# power_supply_module.net
KiCad netlist of a schematic drawn in EAGLE
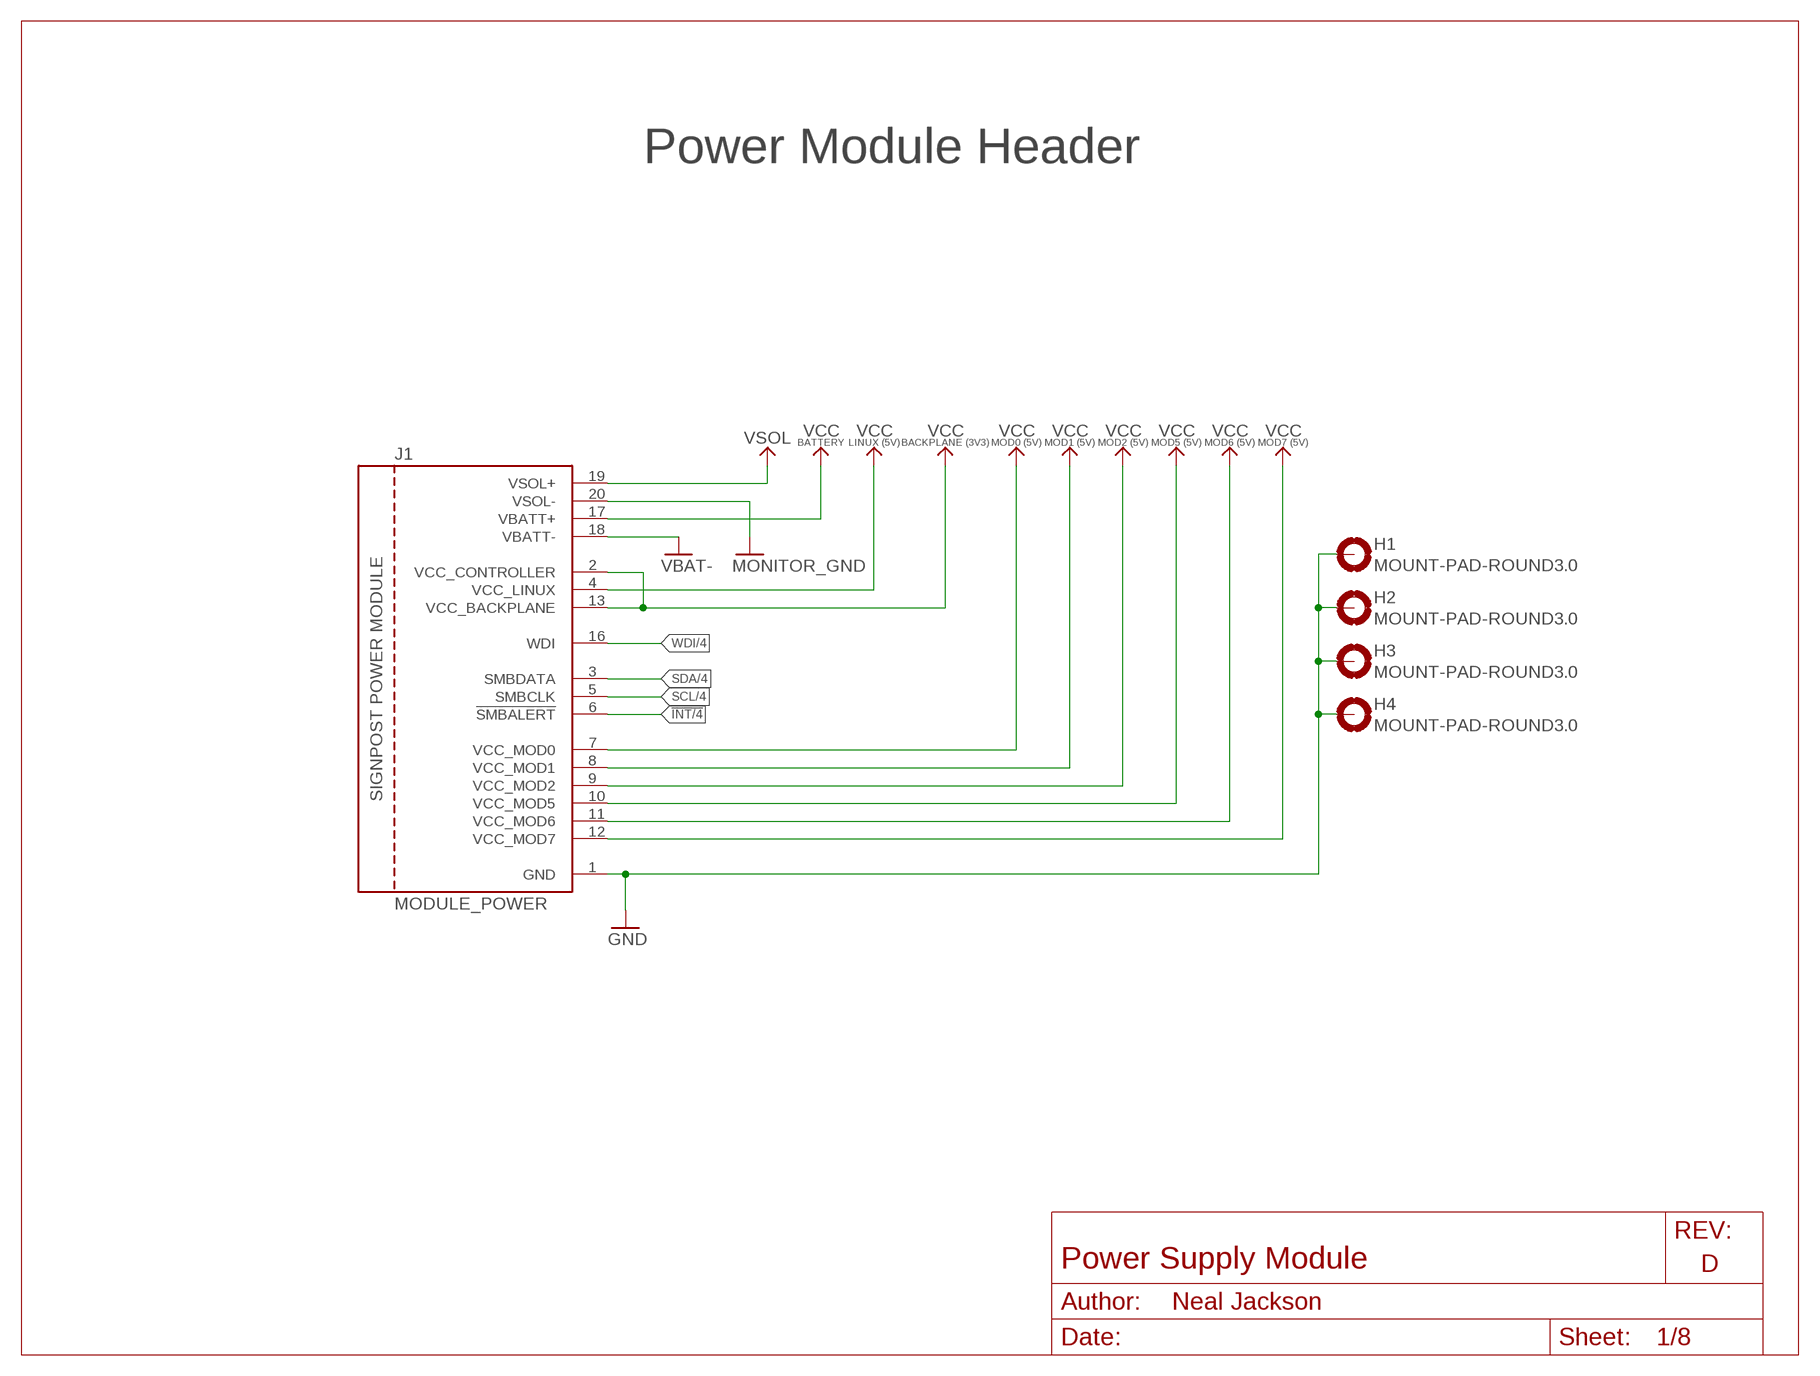
[diagram p0: schematic, sheet 1]
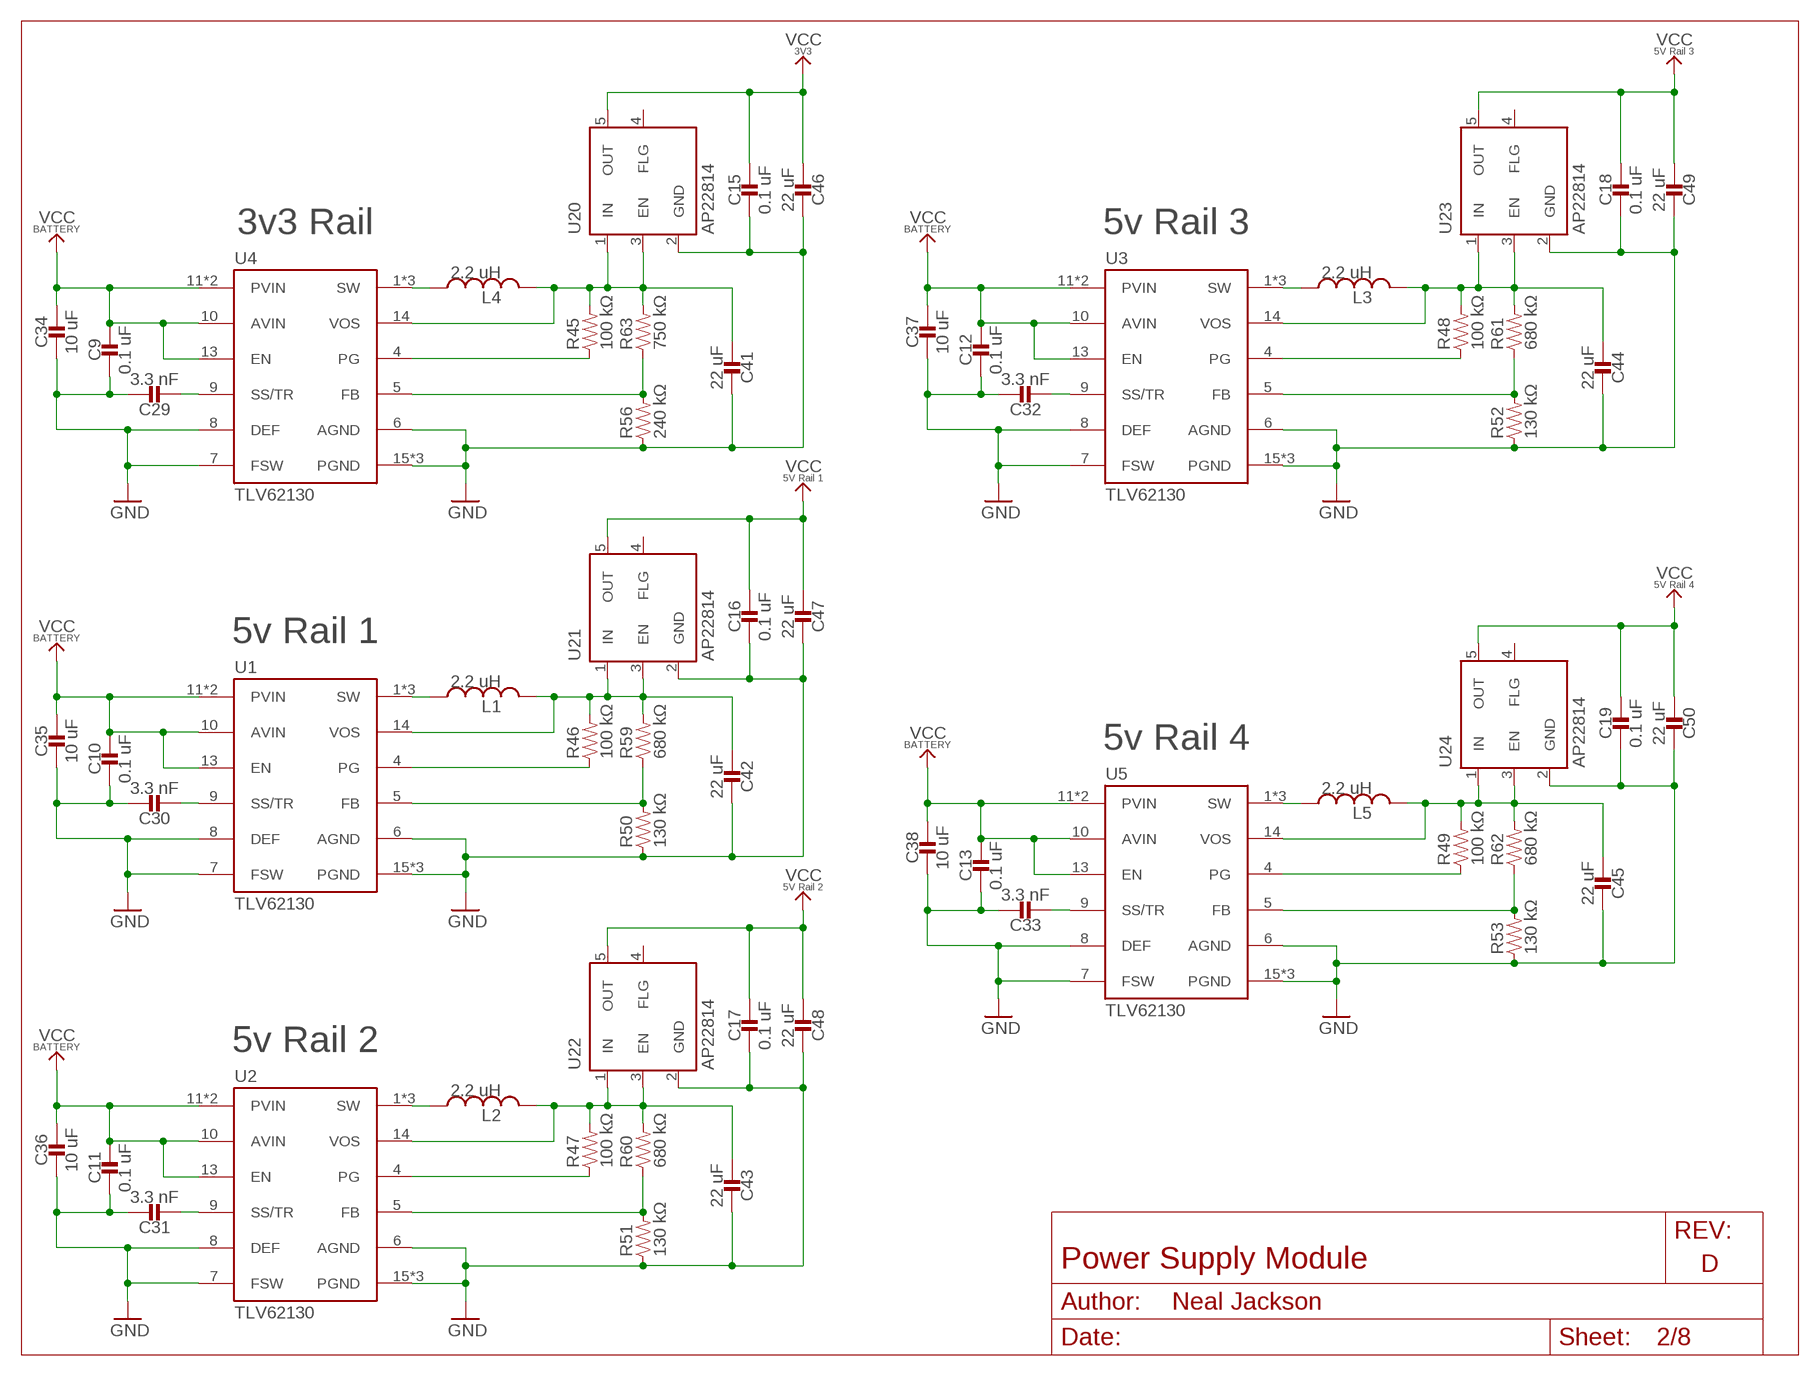
[diagram p1: schematic, sheet 2]
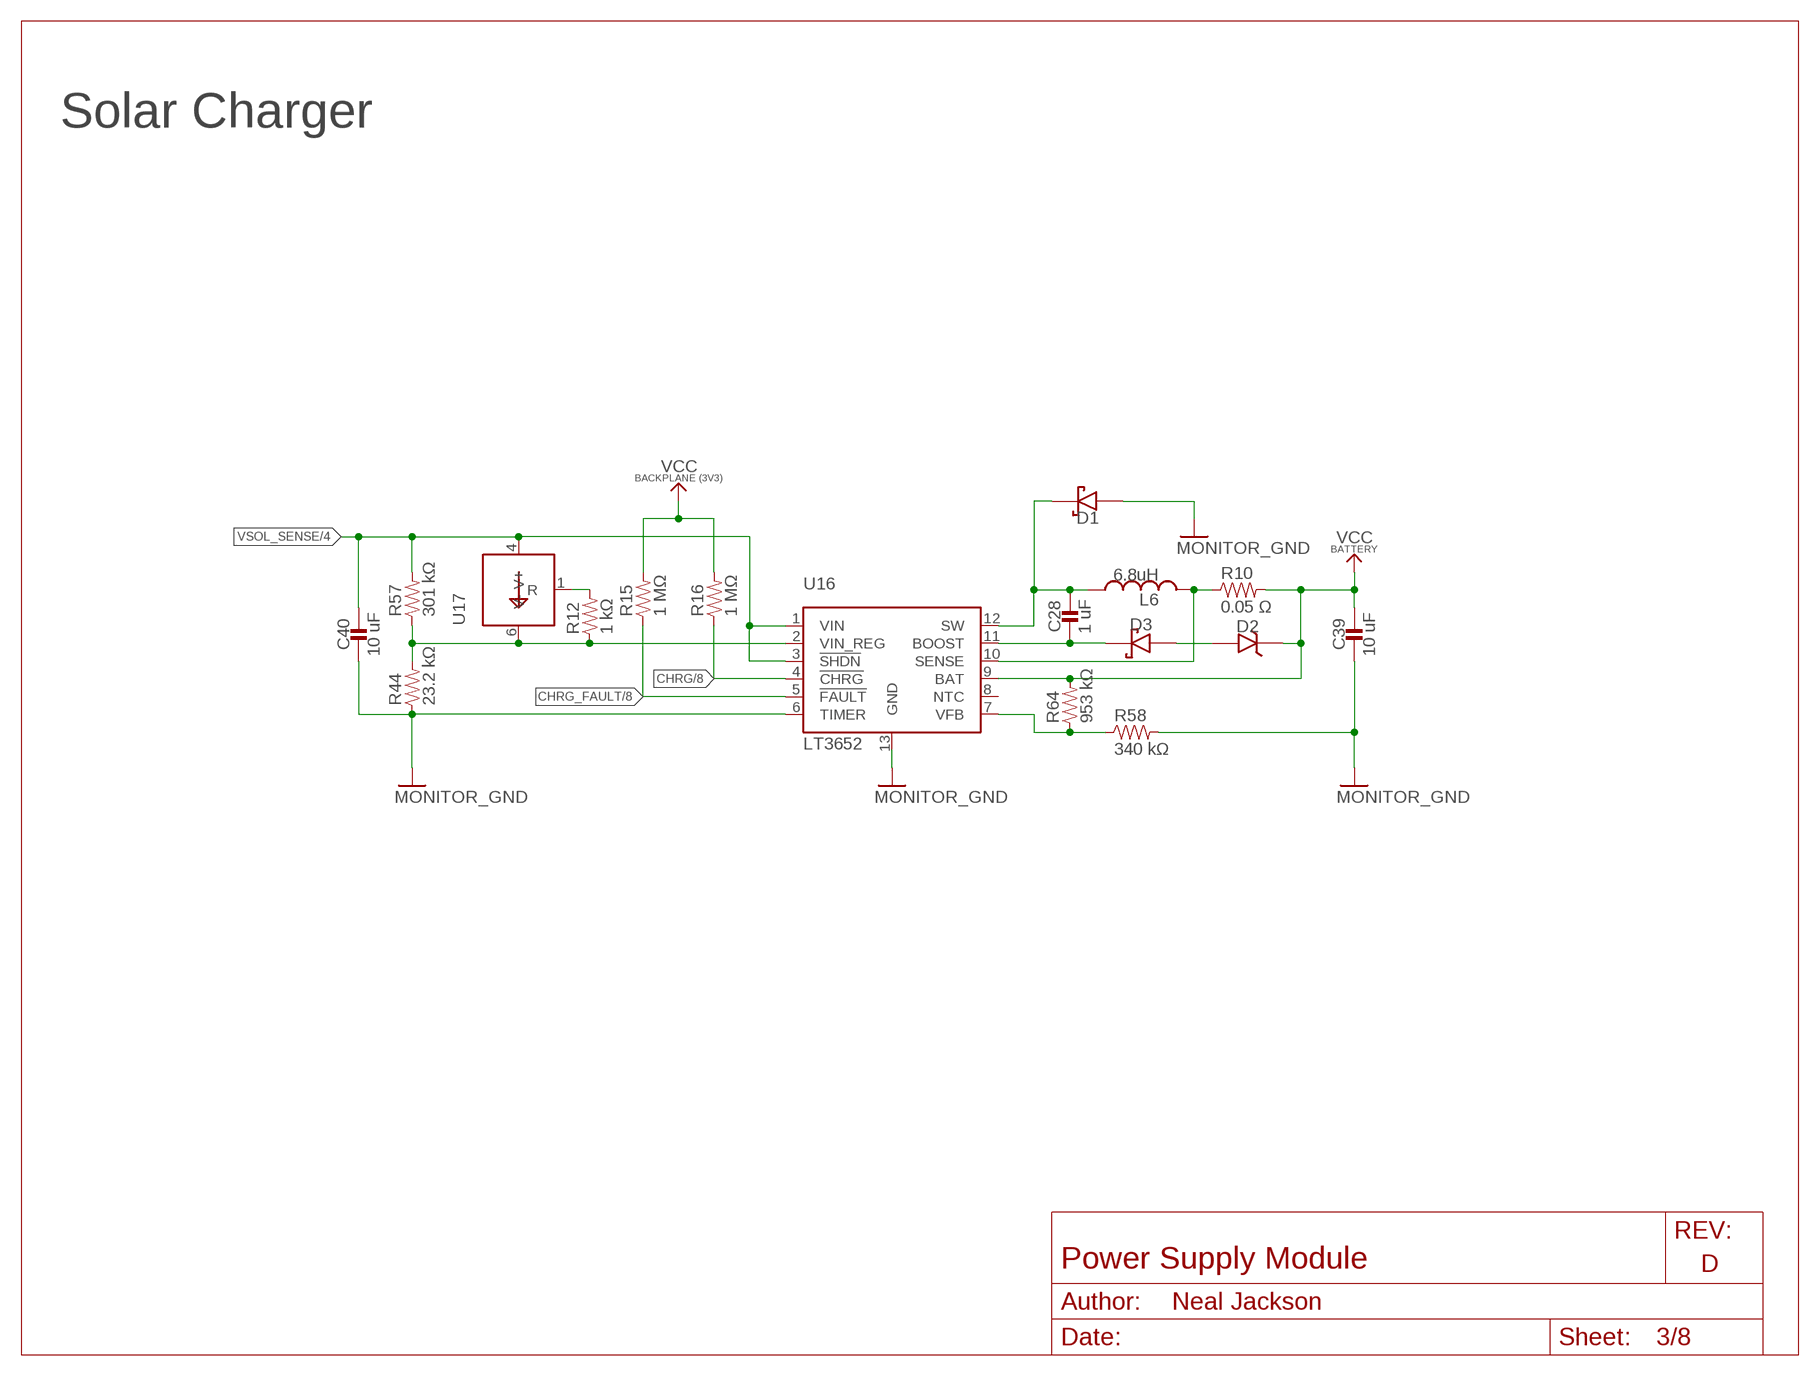
[diagram p2: schematic, sheet 3]
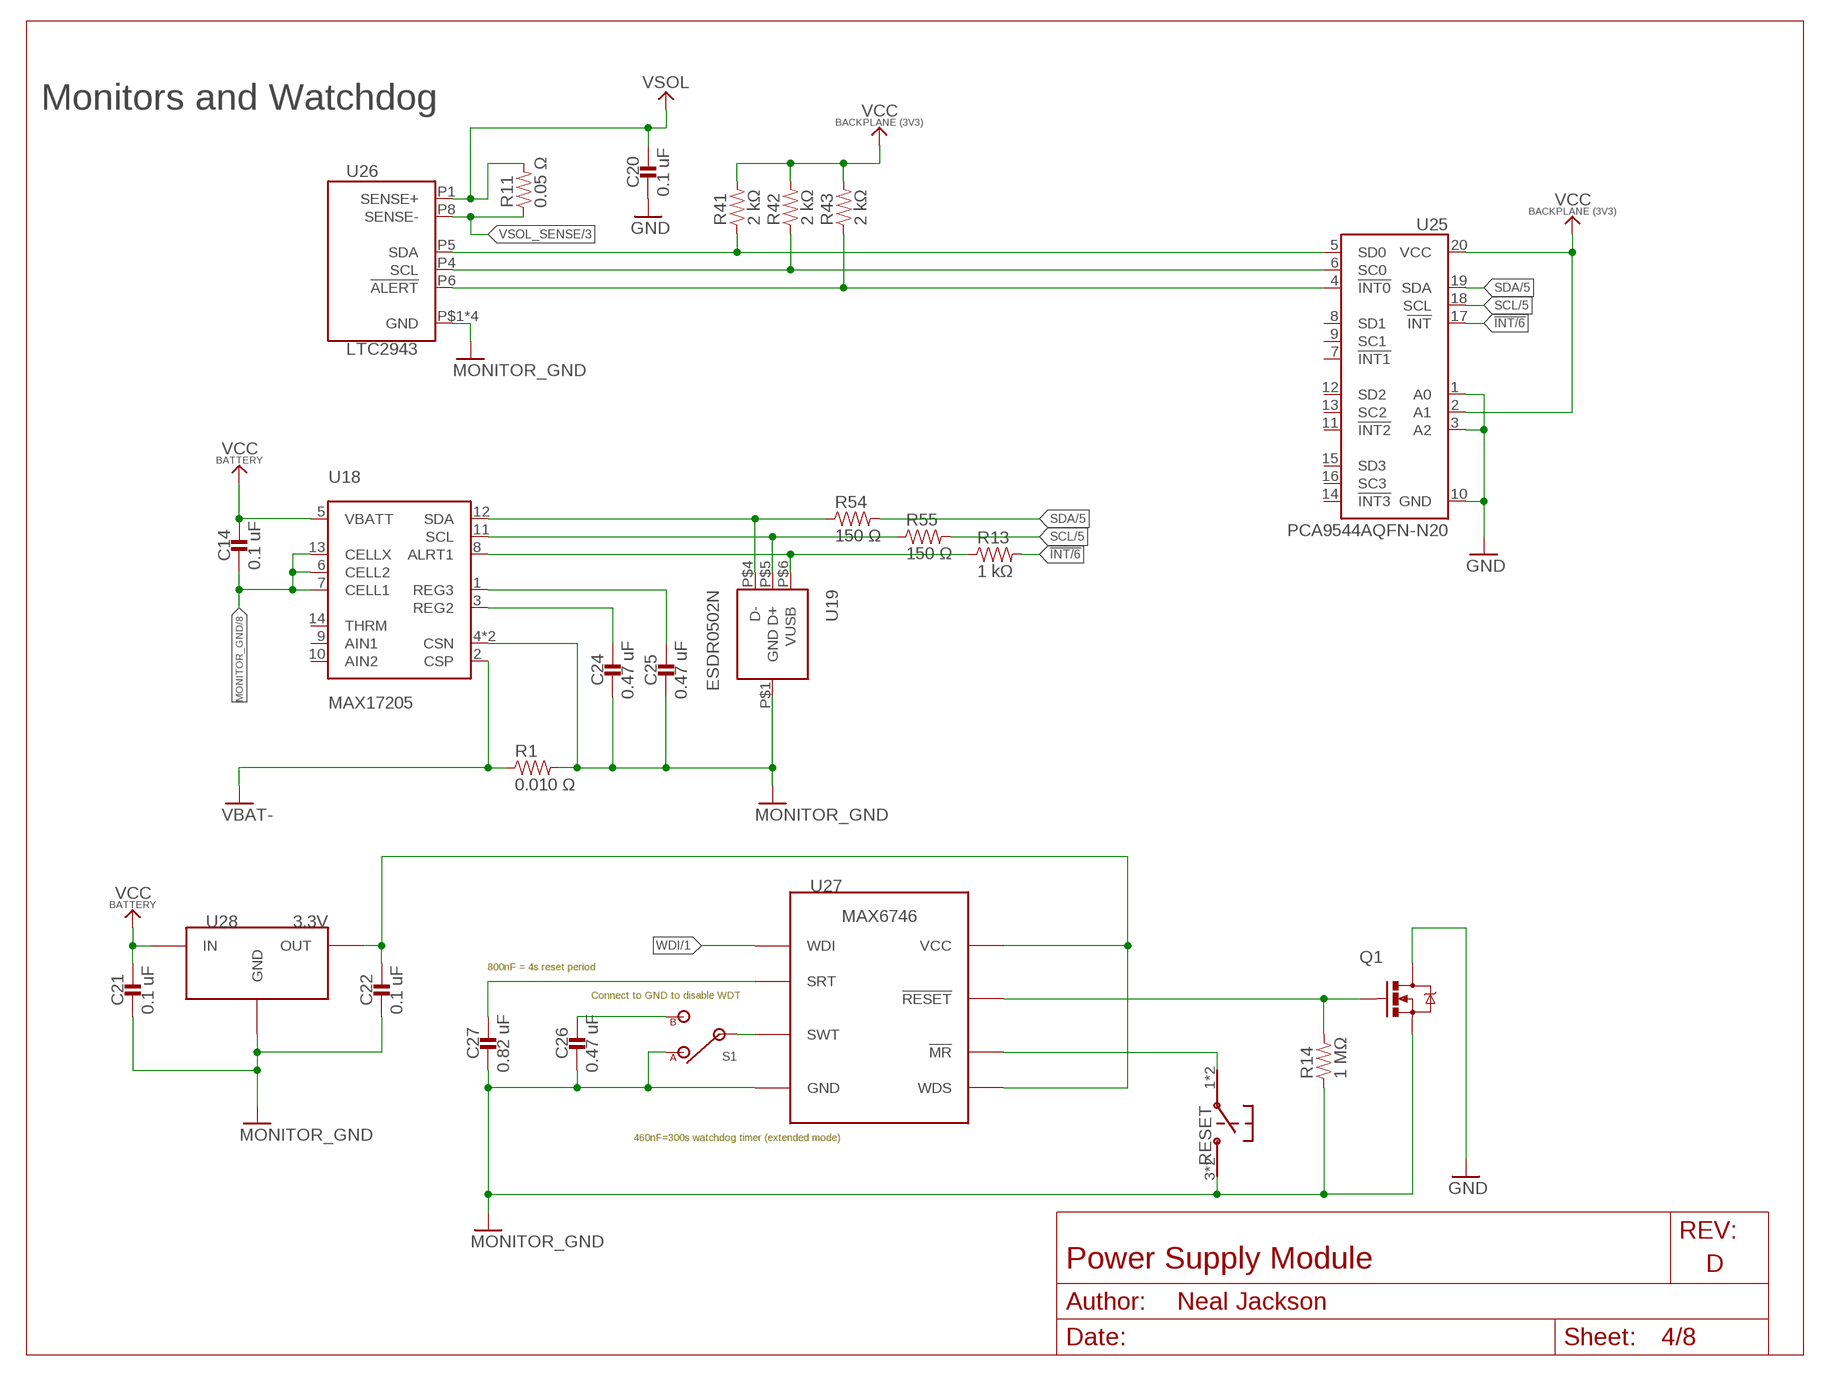
[diagram p3: schematic, sheet 4]
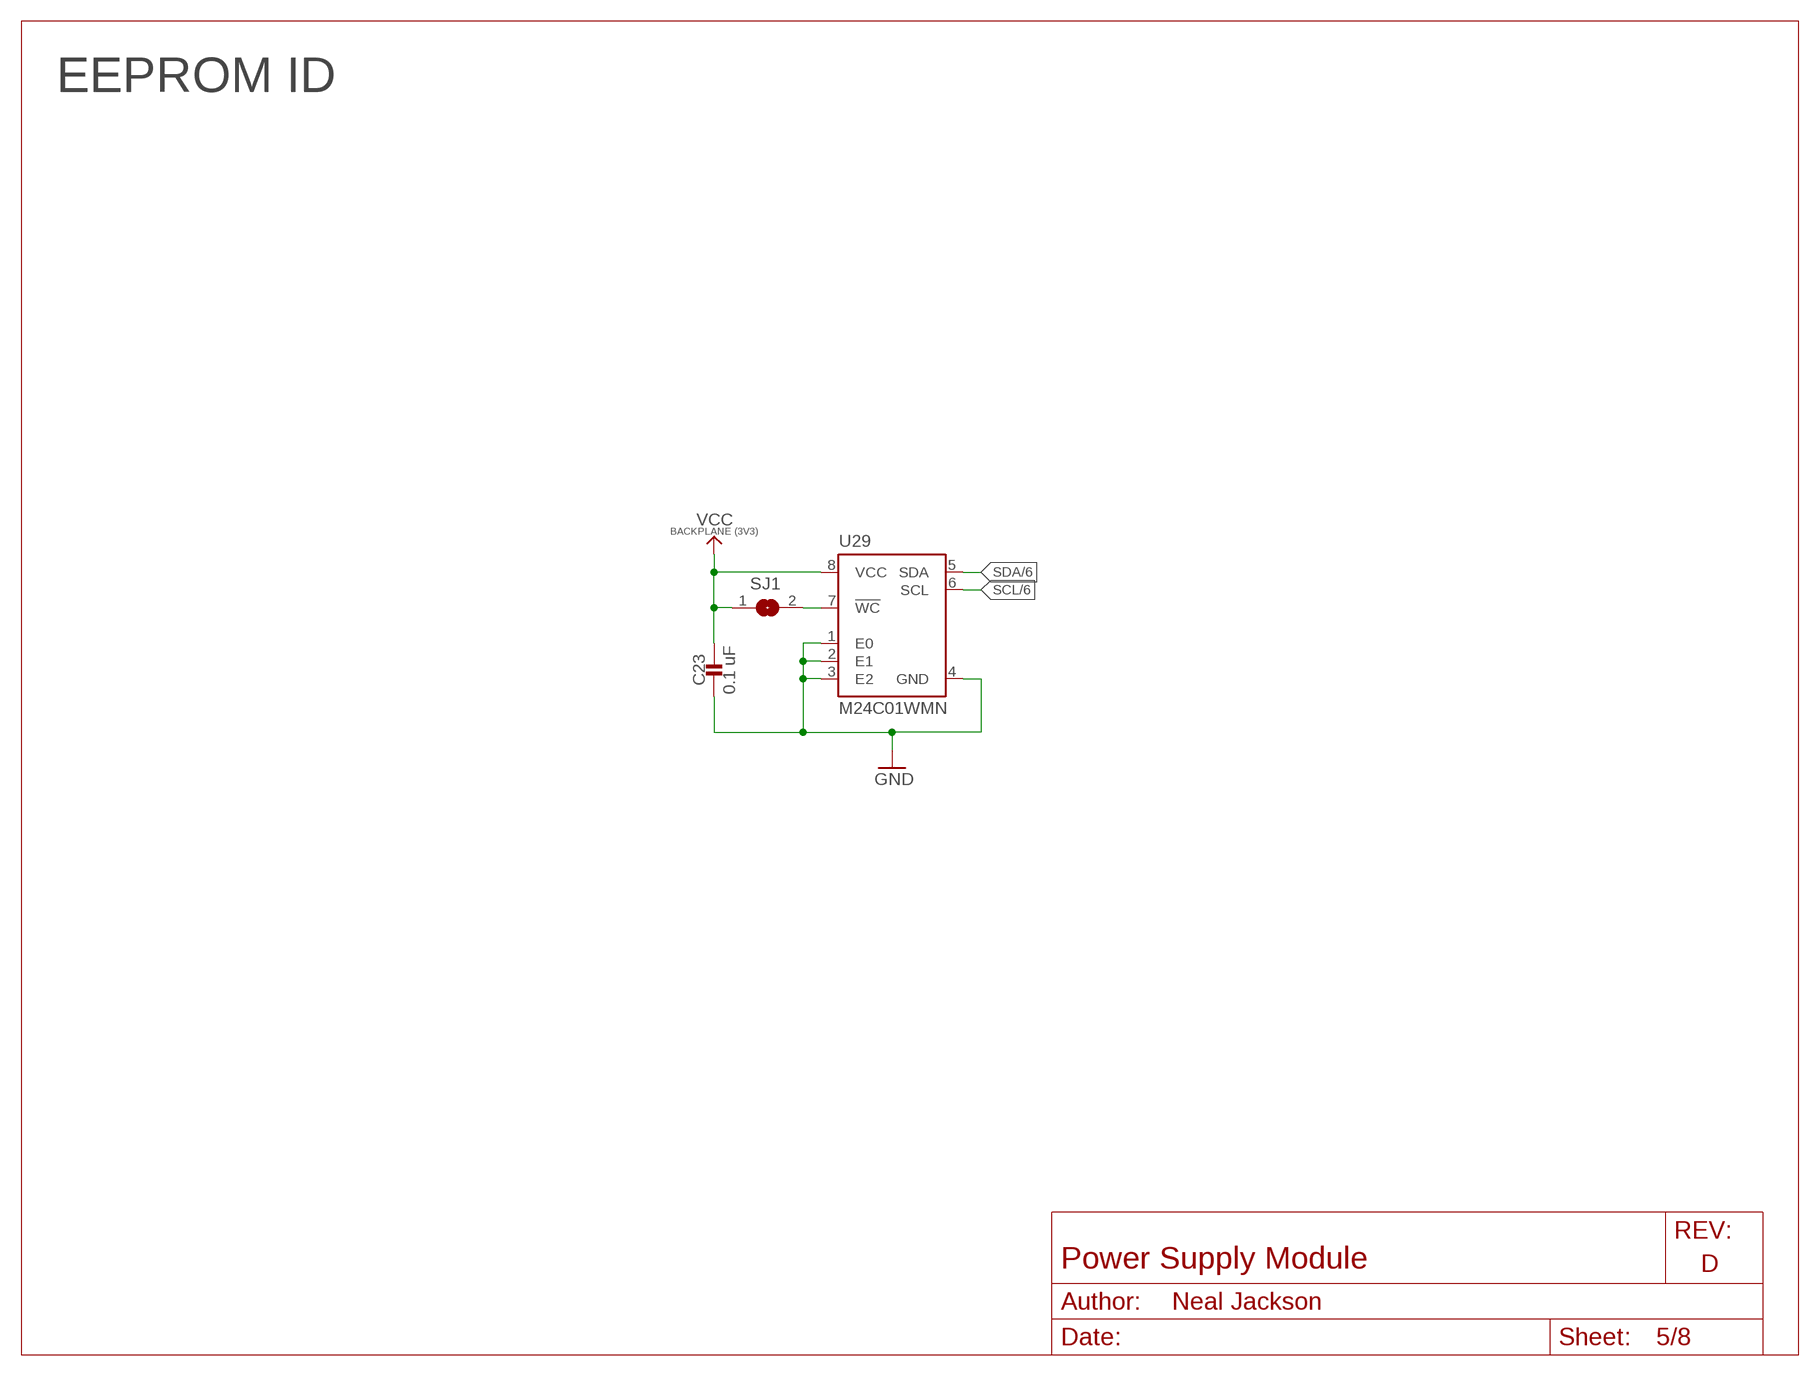
[diagram p4: schematic, sheet 5]
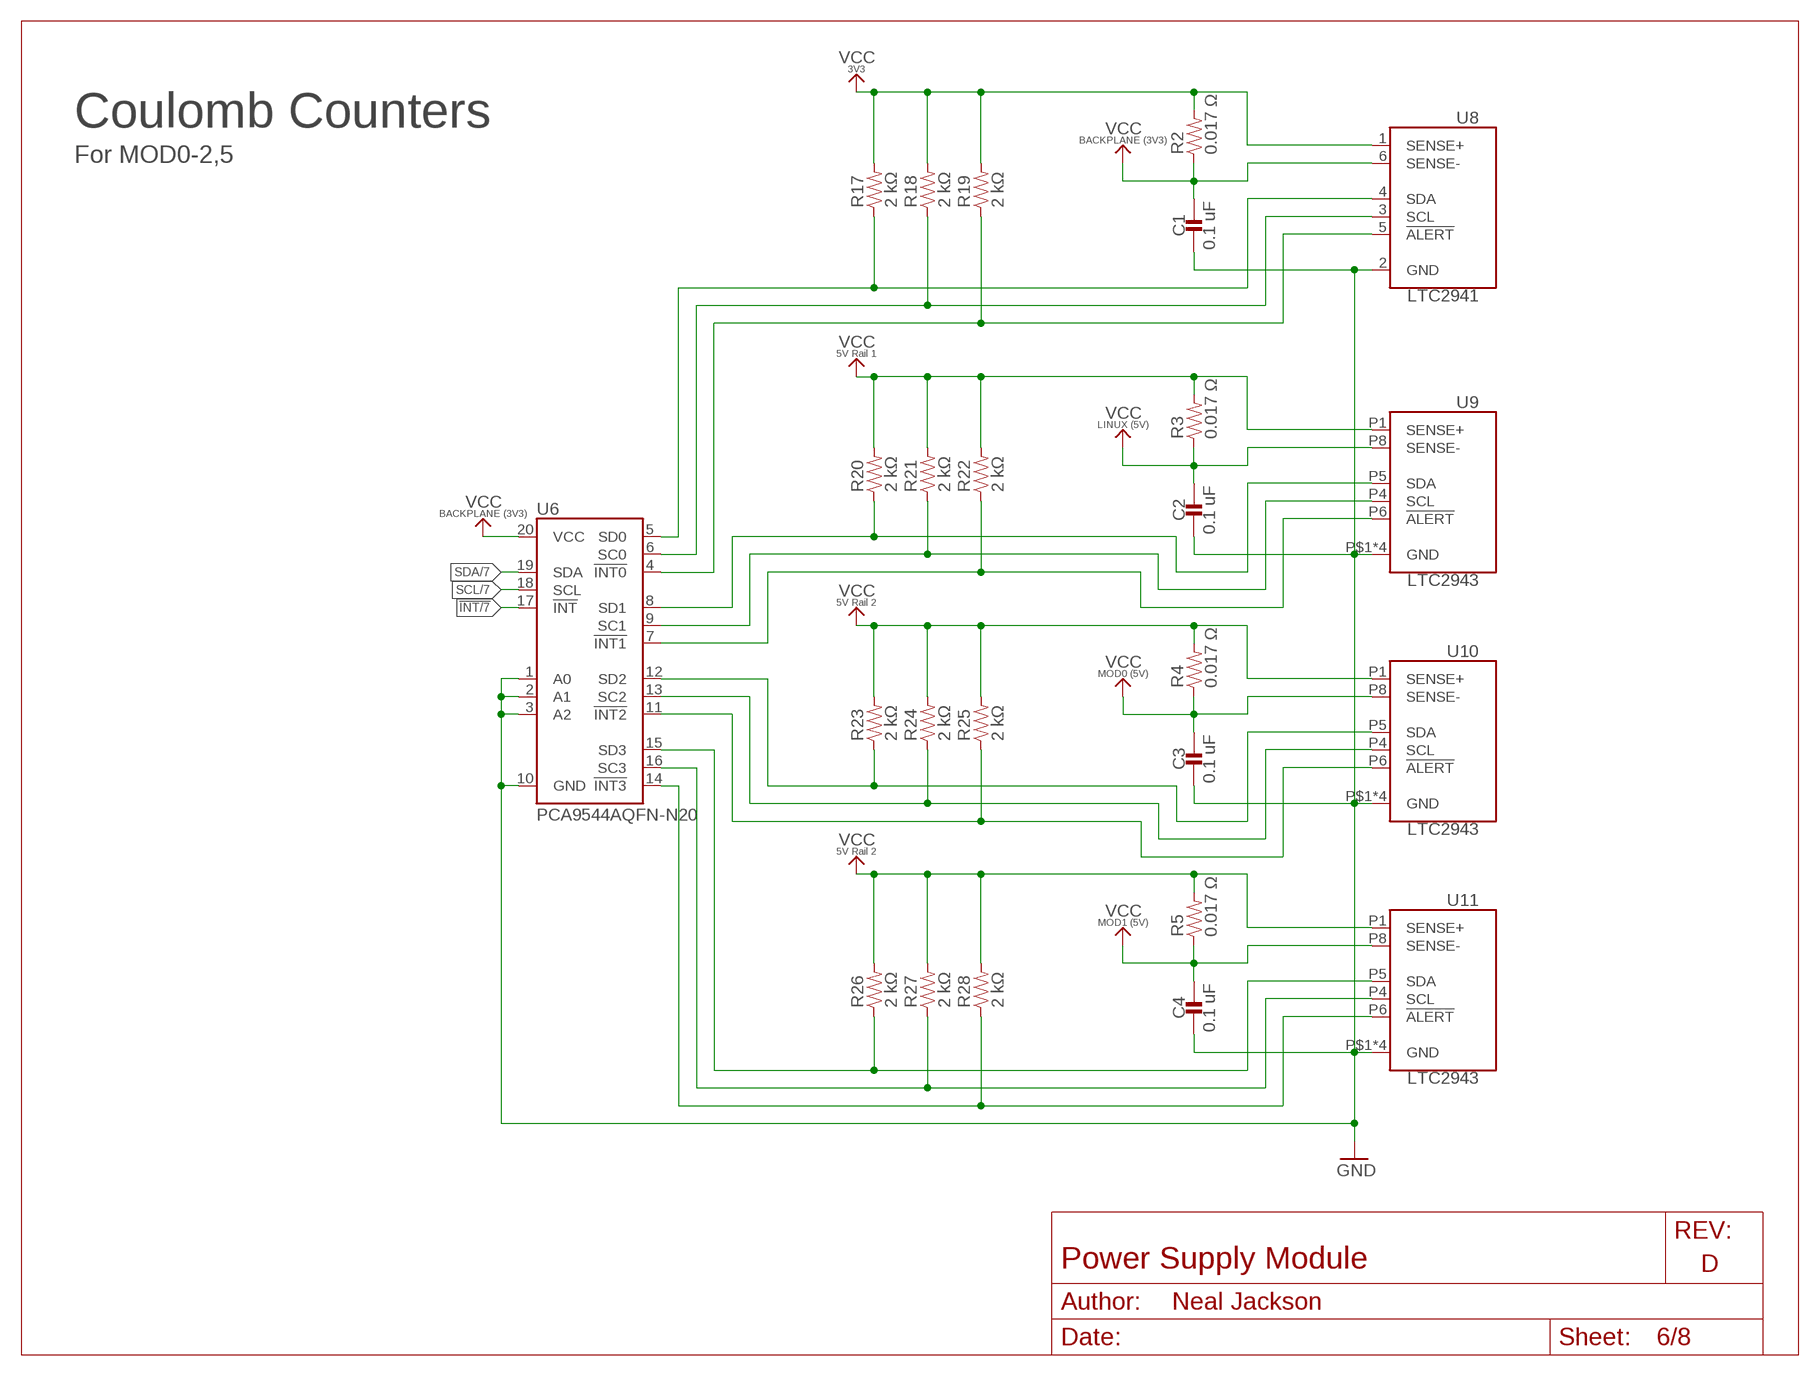
[diagram p5: schematic, sheet 6]
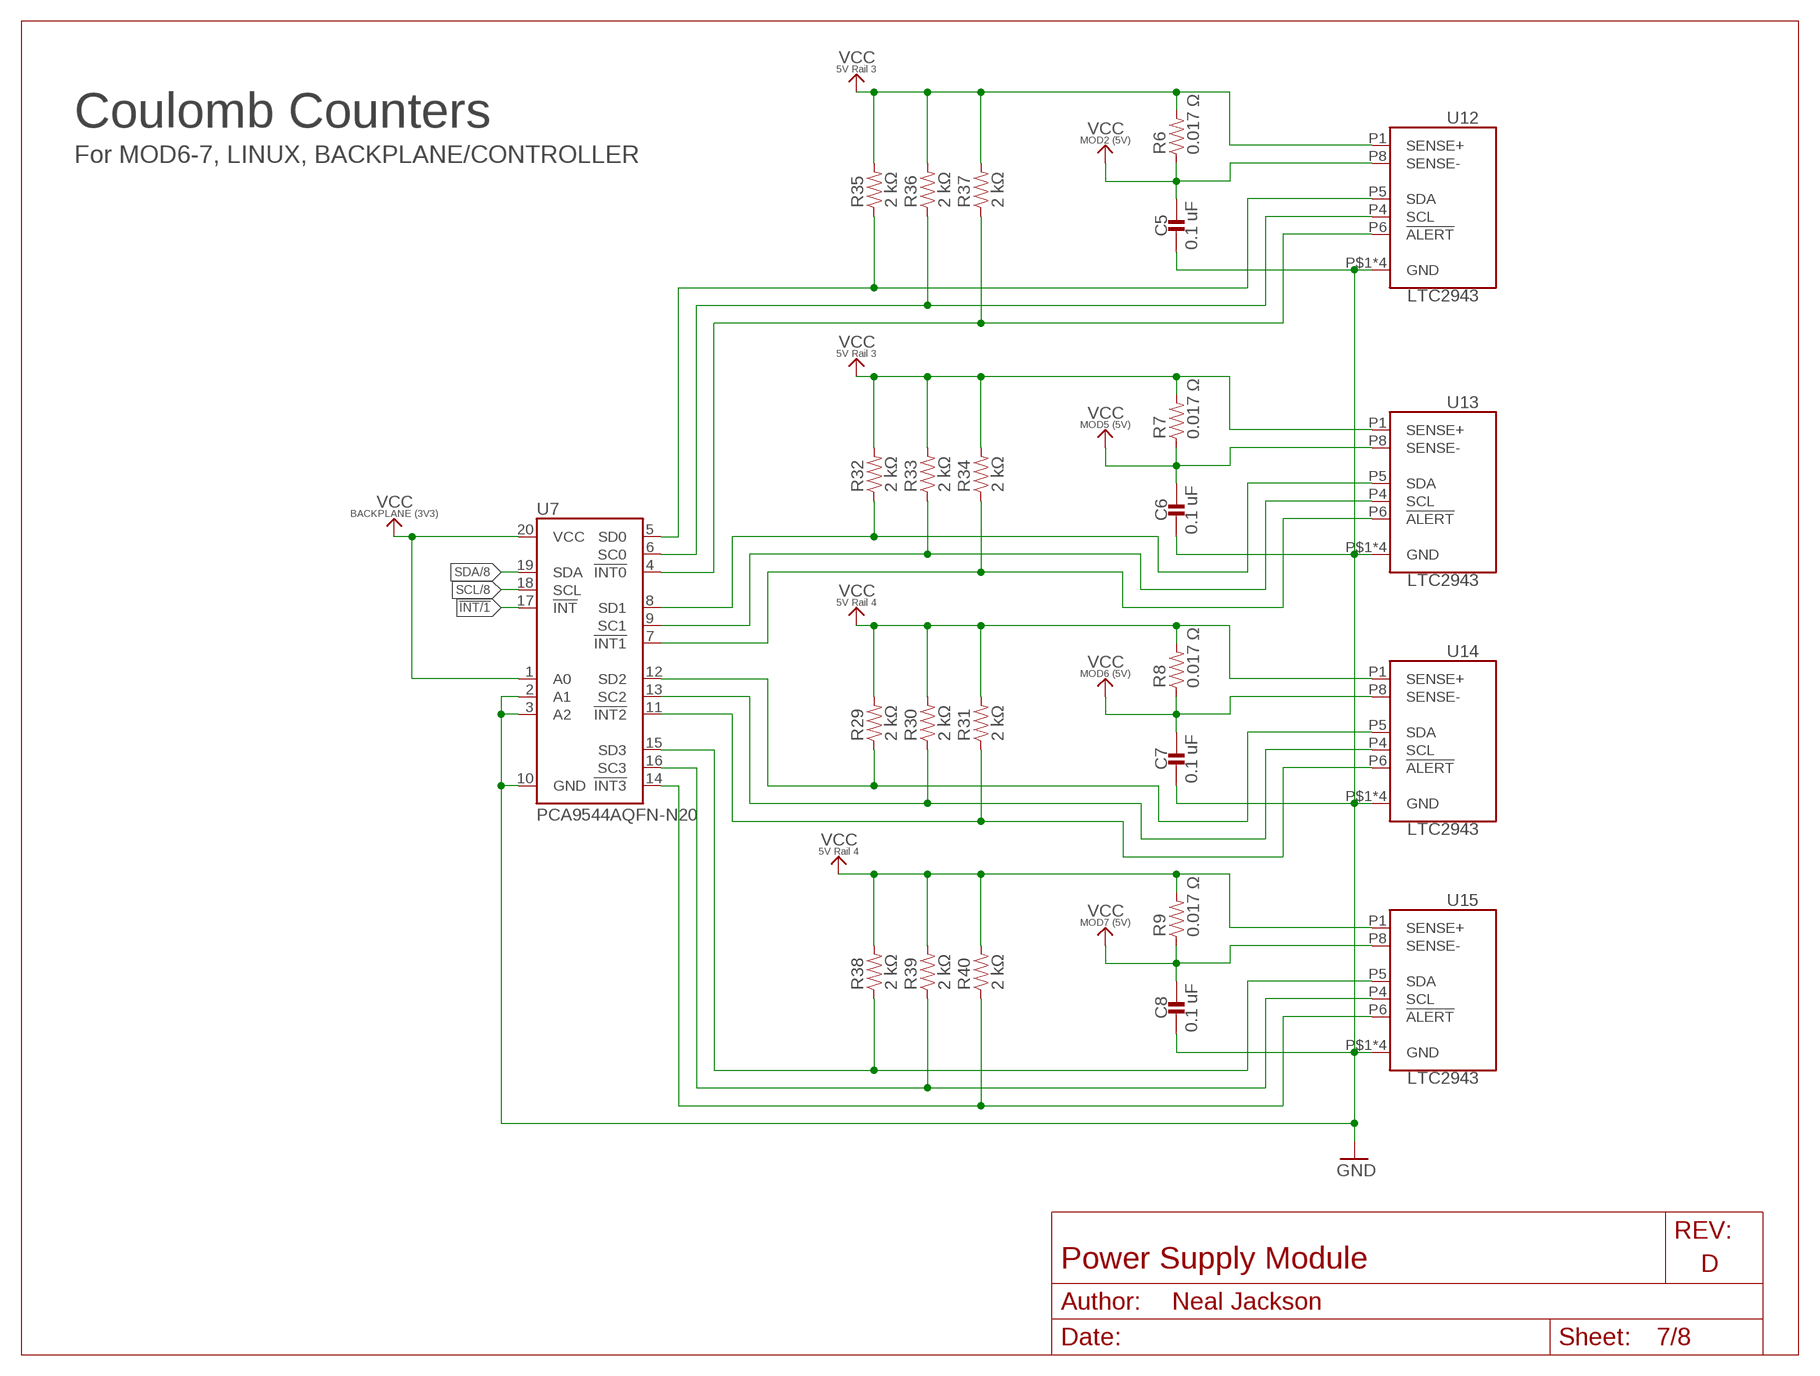
[diagram p6: schematic, sheet 7]
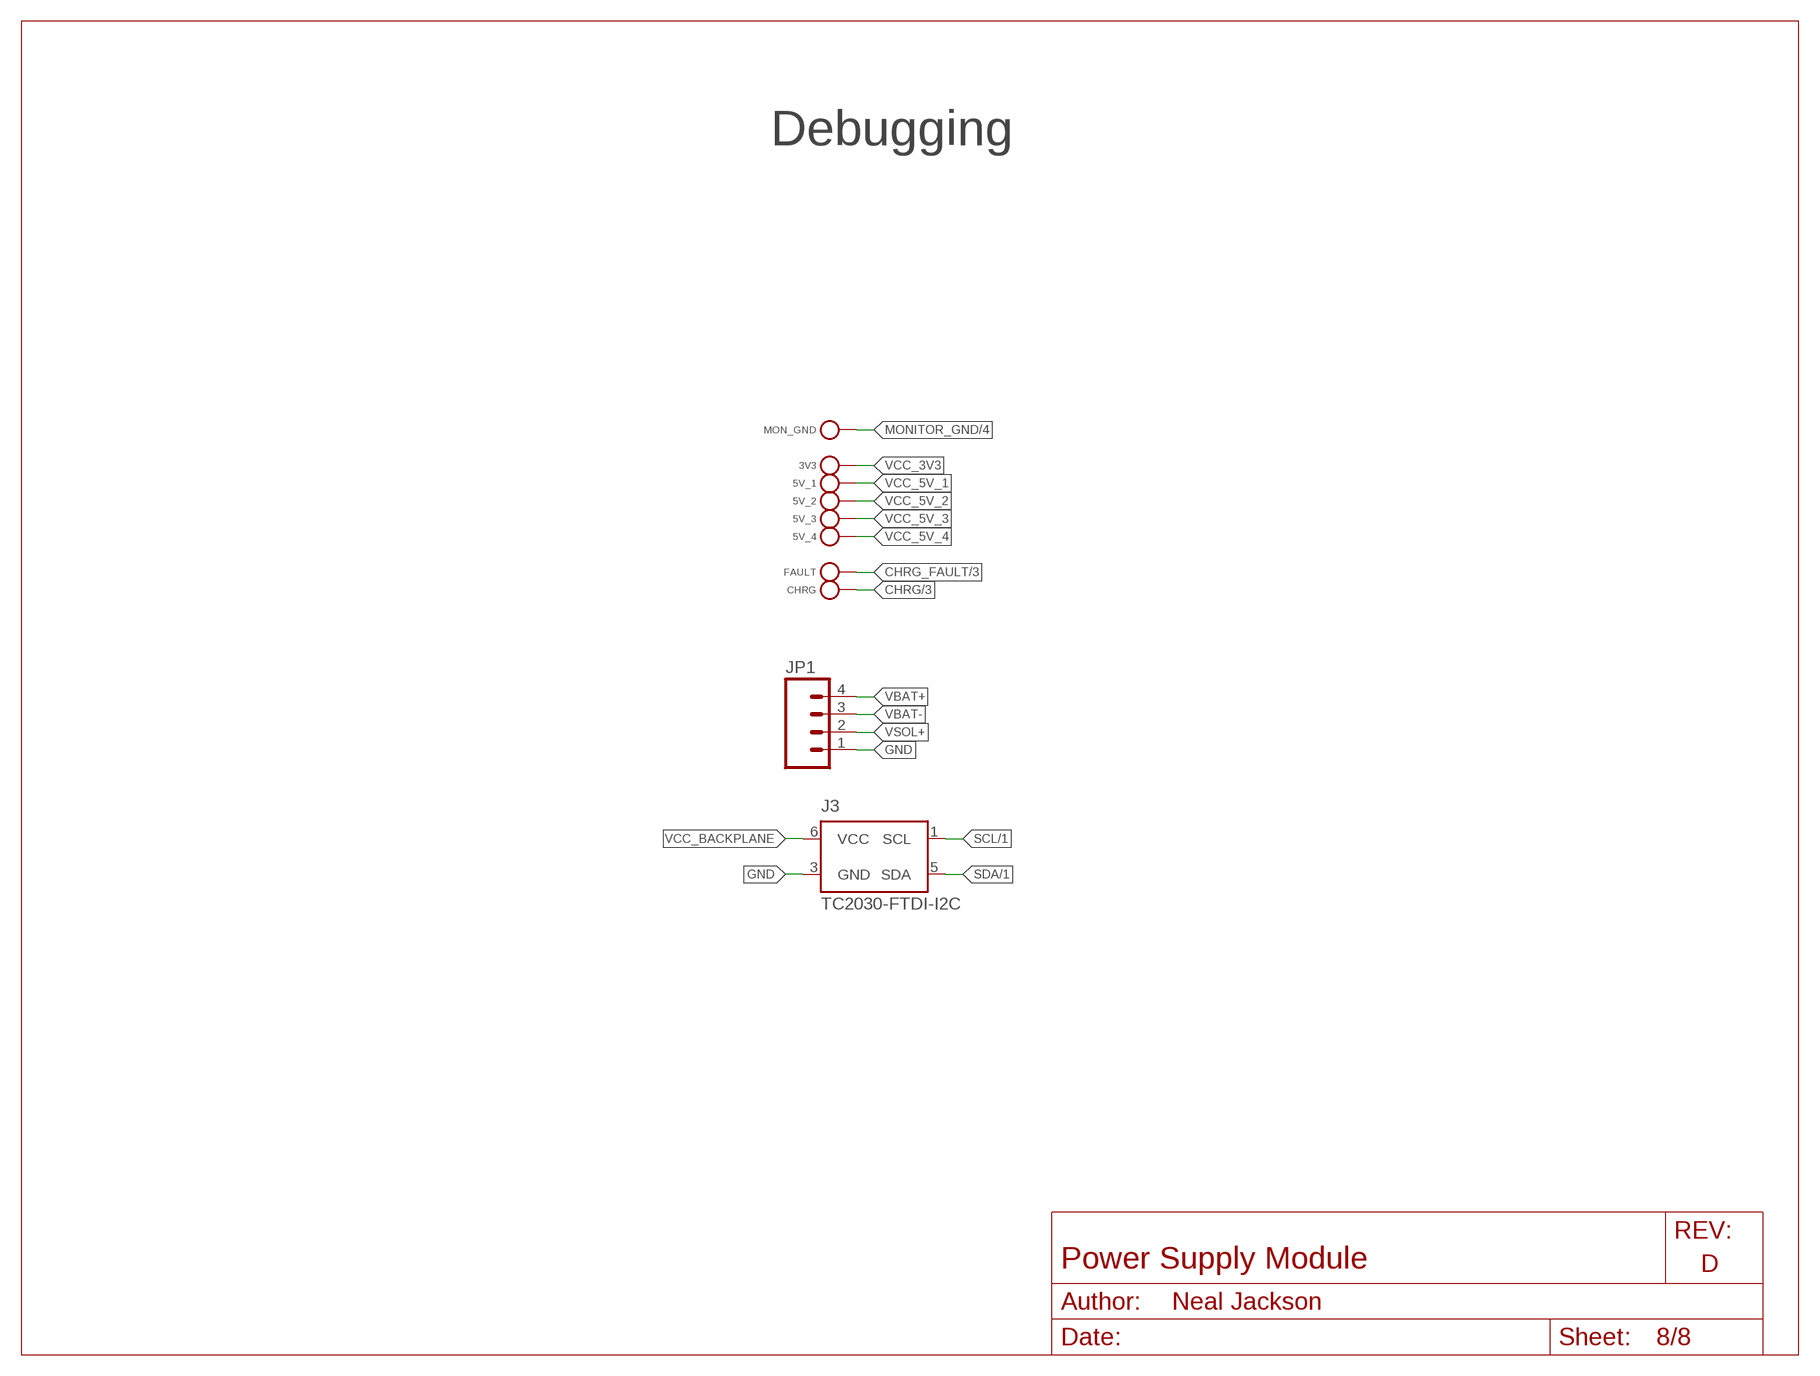
[diagram p7: schematic, sheet 8]

(export (version "E")
  (design (tool "Eeschema 10.0.6"))
  (components
    (comp (ref "3V3")
      (value "TEST_POINT_0.040IN")
      (footprint "eagle-import:TESTPOINT_0.040IN")
      (libsource (lib "eagle-import") (part "TEST_POINT_0.040IN"))
    )
    (comp (ref "5V_1")
      (value "TEST_POINT_0.040IN")
      (footprint "eagle-import:TESTPOINT_0.040IN")
      (libsource (lib "eagle-import") (part "TEST_POINT_0.040IN"))
    )
    (comp (ref "5V_2")
      (value "TEST_POINT_0.040IN")
      (footprint "eagle-import:TESTPOINT_0.040IN")
      (libsource (lib "eagle-import") (part "TEST_POINT_0.040IN"))
    )
    (comp (ref "5V_3")
      (value "TEST_POINT_0.040IN")
      (footprint "eagle-import:TESTPOINT_0.040IN")
      (libsource (lib "eagle-import") (part "TEST_POINT_0.040IN"))
    )
    (comp (ref "5V_4")
      (value "TEST_POINT_0.040IN")
      (footprint "eagle-import:TESTPOINT_0.040IN")
      (libsource (lib "eagle-import") (part "TEST_POINT_0.040IN"))
    )
    (comp (ref "CHRG")
      (value "TEST_POINT_0.040IN")
      (footprint "eagle-import:TESTPOINT_0.040IN")
      (libsource (lib "eagle-import") (part "TEST_POINT_0.040IN"))
    )
    (comp (ref "FAULT")
      (value "TEST_POINT_0.040IN")
      (footprint "eagle-import:TESTPOINT_0.040IN")
      (libsource (lib "eagle-import") (part "TEST_POINT_0.040IN"))
    )
    (comp (ref "J3")
      (value "TC2030-FTDI-I2C")
      (footprint "eagle-import:TC2030-IDC-NL")
      (libsource (lib "eagle-import") (part "TC2030-FTDI-I2C"))
    )
    (comp (ref "JP1")
      (value "M04PTH")
      (footprint "eagle-import:1X04")
      (libsource (lib "eagle-import") (part "M04PTH"))
    )
    (comp (ref "MON_GND")
      (value "TEST_POINT_0.040IN")
      (footprint "eagle-import:TESTPOINT_0.040IN")
      (libsource (lib "eagle-import") (part "TEST_POINT_0.040IN"))
    )
    (comp (ref "C14")
      (value "0.1 uF")
      (footprint "eagle-import:0402_CAP")
      (libsource (lib "eagle-import") (part "CAPACITOR0402_CAP"))
    )
    (comp (ref "C20")
      (value "0.1 uF")
      (footprint "eagle-import:0402_CAP")
      (libsource (lib "eagle-import") (part "CAPACITOR0402_CAP"))
    )
    (comp (ref "C21")
      (value "0.1 uF")
      (footprint "eagle-import:0402_CAP")
      (libsource (lib "eagle-import") (part "CAPACITOR0402_CAP"))
    )
    (comp (ref "C22")
      (value "0.1 uF")
      (footprint "eagle-import:0402_CAP")
      (libsource (lib "eagle-import") (part "CAPACITOR0402_CAP"))
    )
    (comp (ref "C24")
      (value "0.47 uF")
      (footprint "eagle-import:0402_CAP")
      (libsource (lib "eagle-import") (part "CAPACITOR0402_CAP"))
    )
    (comp (ref "C25")
      (value "0.47 uF")
      (footprint "eagle-import:0402_CAP")
      (libsource (lib "eagle-import") (part "CAPACITOR0402_CAP"))
    )
    (comp (ref "C26")
      (value "0.47 uF")
      (footprint "eagle-import:0402_CAP")
      (libsource (lib "eagle-import") (part "CAPACITOR0402_CAP"))
    )
    (comp (ref "C27")
      (value "0.82 uF")
      (footprint "eagle-import:0402_CAP")
      (libsource (lib "eagle-import") (part "CAPACITOR0402_CAP"))
    )
    (comp (ref "Q1")
      (value "MOSFET-NCHANNELFDD8580")
      (footprint "eagle-import:DPAK")
      (libsource (lib "eagle-import") (part "MOSFET-NCHANNELFDD8580"))
    )
    (comp (ref "R1")
      (value "0.010 Ω")
      (footprint "eagle-import:0805_RES")
      (libsource (lib "eagle-import") (part "RESISTOR0805_RES"))
    )
    (comp (ref "R11")
      (value "0.05 Ω")
      (footprint "eagle-import:0805_RES")
      (libsource (lib "eagle-import") (part "RESISTOR0805_RES"))
    )
    (comp (ref "R13")
      (value "1 kΩ")
      (footprint "eagle-import:0402_RES")
      (libsource (lib "eagle-import") (part "RESISTOR0402_RES"))
    )
    (comp (ref "R14")
      (value "1 MΩ")
      (footprint "eagle-import:0402_RES")
      (libsource (lib "eagle-import") (part "RESISTOR0402_RES"))
    )
    (comp (ref "R41")
      (value "2 kΩ")
      (footprint "eagle-import:0402_RES")
      (libsource (lib "eagle-import") (part "RESISTOR0402_RES"))
    )
    (comp (ref "R42")
      (value "2 kΩ")
      (footprint "eagle-import:0402_RES")
      (libsource (lib "eagle-import") (part "RESISTOR0402_RES"))
    )
    (comp (ref "R43")
      (value "2 kΩ")
      (footprint "eagle-import:0402_RES")
      (libsource (lib "eagle-import") (part "RESISTOR0402_RES"))
    )
    (comp (ref "R54")
      (value "150 Ω")
      (footprint "eagle-import:0402_RES")
      (libsource (lib "eagle-import") (part "RESISTOR0402_RES"))
    )
    (comp (ref "R55")
      (value "150 Ω")
      (footprint "eagle-import:0402_RES")
      (libsource (lib "eagle-import") (part "RESISTOR0402_RES"))
    )
    (comp (ref "RESET")
      (value "PTS810SJ")
      (footprint "eagle-import:PTS810SJ")
      (libsource (lib "eagle-import") (part "PTS810SJ"))
    )
    (comp (ref "S1")
      (value "TE_SSA12/SPDT")
      (footprint "eagle-import:TE_SSA12_SPDT")
      (libsource (lib "eagle-import") (part "TE_SSA12/SPDT"))
    )
    (comp (ref "U18")
      (value "MAX17205")
      (footprint "eagle-import:14-TDFN")
      (libsource (lib "eagle-import") (part "MAX17205"))
    )
    (comp (ref "U19")
      (value "ESDR0502N")
      (footprint "eagle-import:UDFN-6")
      (libsource (lib "eagle-import") (part "ESDR0502N"))
    )
    (comp (ref "U25")
      (value "PCA9544AQFN-N20")
      (footprint "eagle-import:QFN-N20")
      (libsource (lib "eagle-import") (part "PCA9544AQFN-N20"))
    )
    (comp (ref "U26")
      (value "LTC2943")
      (footprint "eagle-import:DFN-8")
      (libsource (lib "eagle-import") (part "LTC2943"))
    )
    (comp (ref "U27")
      (value "MAX6746")
      (footprint "eagle-import:SOT-23-8")
      (libsource (lib "eagle-import") (part "MAX6746"))
    )
    (comp (ref "U28")
      (value "3.3V")
      (footprint "eagle-import:SOT-23")
      (fields (field (name "DIGIKEY") "ZMR330FCT-ND"))
      (libsource (lib "eagle-import") (part "TILM34803.3V"))
    )
    (comp (ref "H1")
      (value "MOUNT-PAD-ROUND3.0")
      (footprint "eagle-import:3,0-PAD")
      (libsource (lib "eagle-import") (part "MOUNT-PAD-ROUND3.0"))
    )
    (comp (ref "H2")
      (value "MOUNT-PAD-ROUND3.0")
      (footprint "eagle-import:3,0-PAD")
      (libsource (lib "eagle-import") (part "MOUNT-PAD-ROUND3.0"))
    )
    (comp (ref "H3")
      (value "MOUNT-PAD-ROUND3.0")
      (footprint "eagle-import:3,0-PAD")
      (libsource (lib "eagle-import") (part "MOUNT-PAD-ROUND3.0"))
    )
    (comp (ref "H4")
      (value "MOUNT-PAD-ROUND3.0")
      (footprint "eagle-import:3,0-PAD")
      (libsource (lib "eagle-import") (part "MOUNT-PAD-ROUND3.0"))
    )
    (comp (ref "J1")
      (value "MODULE_POWER")
      (footprint "eagle-import:MODULE_POWER")
      (libsource (lib "eagle-import") (part "MODULE_POWER"))
    )
    (comp (ref "C9")
      (value "0.1 uF")
      (footprint "eagle-import:0402_CAP")
      (libsource (lib "eagle-import") (part "CAPACITOR0402_CAP"))
    )
    (comp (ref "C10")
      (value "0.1 uF")
      (footprint "eagle-import:0402_CAP")
      (libsource (lib "eagle-import") (part "CAPACITOR0402_CAP"))
    )
    (comp (ref "C11")
      (value "0.1 uF")
      (footprint "eagle-import:0402_CAP")
      (libsource (lib "eagle-import") (part "CAPACITOR0402_CAP"))
    )
    (comp (ref "C12")
      (value "0.1 uF")
      (footprint "eagle-import:0402_CAP")
      (libsource (lib "eagle-import") (part "CAPACITOR0402_CAP"))
    )
    (comp (ref "C13")
      (value "0.1 uF")
      (footprint "eagle-import:0402_CAP")
      (libsource (lib "eagle-import") (part "CAPACITOR0402_CAP"))
    )
    (comp (ref "C15")
      (value "0.1 uF")
      (footprint "eagle-import:0402_CAP")
      (libsource (lib "eagle-import") (part "CAPACITOR0402_CAP"))
    )
    (comp (ref "C16")
      (value "0.1 uF")
      (footprint "eagle-import:0402_CAP")
      (libsource (lib "eagle-import") (part "CAPACITOR0402_CAP"))
    )
    (comp (ref "C17")
      (value "0.1 uF")
      (footprint "eagle-import:0402_CAP")
      (libsource (lib "eagle-import") (part "CAPACITOR0402_CAP"))
    )
    (comp (ref "C18")
      (value "0.1 uF")
      (footprint "eagle-import:0402_CAP")
      (libsource (lib "eagle-import") (part "CAPACITOR0402_CAP"))
    )
    (comp (ref "C19")
      (value "0.1 uF")
      (footprint "eagle-import:0402_CAP")
      (libsource (lib "eagle-import") (part "CAPACITOR0402_CAP"))
    )
    (comp (ref "C29")
      (value "3.3 nF")
      (footprint "eagle-import:0402_CAP")
      (libsource (lib "eagle-import") (part "CAPACITOR0402_CAP"))
    )
    (comp (ref "C30")
      (value "3.3 nF")
      (footprint "eagle-import:0402_CAP")
      (libsource (lib "eagle-import") (part "CAPACITOR0402_CAP"))
    )
    (comp (ref "C31")
      (value "3.3 nF")
      (footprint "eagle-import:0402_CAP")
      (libsource (lib "eagle-import") (part "CAPACITOR0402_CAP"))
    )
    (comp (ref "C32")
      (value "3.3 nF")
      (footprint "eagle-import:0402_CAP")
      (libsource (lib "eagle-import") (part "CAPACITOR0402_CAP"))
    )
    (comp (ref "C33")
      (value "3.3 nF")
      (footprint "eagle-import:0402_CAP")
      (libsource (lib "eagle-import") (part "CAPACITOR0402_CAP"))
    )
    (comp (ref "C34")
      (value "10 uF")
      (footprint "eagle-import:0805_CAP")
      (libsource (lib "eagle-import") (part "CAPACITOR0805_CAP"))
    )
    (comp (ref "C35")
      (value "10 uF")
      (footprint "eagle-import:0805_CAP")
      (libsource (lib "eagle-import") (part "CAPACITOR0805_CAP"))
    )
    (comp (ref "C36")
      (value "10 uF")
      (footprint "eagle-import:0805_CAP")
      (libsource (lib "eagle-import") (part "CAPACITOR0805_CAP"))
    )
    (comp (ref "C37")
      (value "10 uF")
      (footprint "eagle-import:0805_CAP")
      (libsource (lib "eagle-import") (part "CAPACITOR0805_CAP"))
    )
    (comp (ref "C38")
      (value "10 uF")
      (footprint "eagle-import:0805_CAP")
      (libsource (lib "eagle-import") (part "CAPACITOR0805_CAP"))
    )
    (comp (ref "C41")
      (value "22 uF")
      (footprint "eagle-import:0603_CAP")
      (libsource (lib "eagle-import") (part "CAPACITOR0603_CAP"))
    )
    (comp (ref "C42")
      (value "22 uF")
      (footprint "eagle-import:0603_CAP")
      (libsource (lib "eagle-import") (part "CAPACITOR0603_CAP"))
    )
    (comp (ref "C43")
      (value "22 uF")
      (footprint "eagle-import:0603_CAP")
      (libsource (lib "eagle-import") (part "CAPACITOR0603_CAP"))
    )
    (comp (ref "C44")
      (value "22 uF")
      (footprint "eagle-import:0603_CAP")
      (libsource (lib "eagle-import") (part "CAPACITOR0603_CAP"))
    )
    (comp (ref "C45")
      (value "22 uF")
      (footprint "eagle-import:0603_CAP")
      (libsource (lib "eagle-import") (part "CAPACITOR0603_CAP"))
    )
    (comp (ref "C46")
      (value "22 uF")
      (footprint "eagle-import:0603_CAP")
      (libsource (lib "eagle-import") (part "CAPACITOR0603_CAP"))
    )
    (comp (ref "C47")
      (value "22 uF")
      (footprint "eagle-import:0603_CAP")
      (libsource (lib "eagle-import") (part "CAPACITOR0603_CAP"))
    )
    (comp (ref "C48")
      (value "22 uF")
      (footprint "eagle-import:0603_CAP")
      (libsource (lib "eagle-import") (part "CAPACITOR0603_CAP"))
    )
    (comp (ref "C49")
      (value "22 uF")
      (footprint "eagle-import:0603_CAP")
      (libsource (lib "eagle-import") (part "CAPACITOR0603_CAP"))
    )
    (comp (ref "C50")
      (value "22 uF")
      (footprint "eagle-import:0603_CAP")
      (libsource (lib "eagle-import") (part "CAPACITOR0603_CAP"))
    )
    (comp (ref "L1")
      (value "2.2 uH")
      (footprint "eagle-import:IHL-1212BZ-11")
      (libsource (lib "eagle-import") (part "INDUCTORIHL"))
    )
    (comp (ref "L2")
      (value "2.2 uH")
      (footprint "eagle-import:IHL-1212BZ-11")
      (libsource (lib "eagle-import") (part "INDUCTORIHL"))
    )
    (comp (ref "L3")
      (value "2.2 uH")
      (footprint "eagle-import:IHL-1212BZ-11")
      (libsource (lib "eagle-import") (part "INDUCTORIHL"))
    )
    (comp (ref "L4")
      (value "2.2 uH")
      (footprint "eagle-import:IHL-1212BZ-11")
      (libsource (lib "eagle-import") (part "INDUCTORIHL"))
    )
    (comp (ref "L5")
      (value "2.2 uH")
      (footprint "eagle-import:IHL-1212BZ-11")
      (libsource (lib "eagle-import") (part "INDUCTORIHL"))
    )
    (comp (ref "R45")
      (value "100 kΩ")
      (footprint "eagle-import:0402_RES")
      (libsource (lib "eagle-import") (part "RESISTOR0402_RES"))
    )
    (comp (ref "R46")
      (value "100 kΩ")
      (footprint "eagle-import:0402_RES")
      (libsource (lib "eagle-import") (part "RESISTOR0402_RES"))
    )
    (comp (ref "R47")
      (value "100 kΩ")
      (footprint "eagle-import:0402_RES")
      (libsource (lib "eagle-import") (part "RESISTOR0402_RES"))
    )
    (comp (ref "R48")
      (value "100 kΩ")
      (footprint "eagle-import:0402_RES")
      (libsource (lib "eagle-import") (part "RESISTOR0402_RES"))
    )
    (comp (ref "R49")
      (value "100 kΩ")
      (footprint "eagle-import:0402_RES")
      (libsource (lib "eagle-import") (part "RESISTOR0402_RES"))
    )
    (comp (ref "R50")
      (value "130 kΩ")
      (footprint "eagle-import:0402_RES")
      (libsource (lib "eagle-import") (part "RESISTOR0402_RES"))
    )
    (comp (ref "R51")
      (value "130 kΩ")
      (footprint "eagle-import:0402_RES")
      (libsource (lib "eagle-import") (part "RESISTOR0402_RES"))
    )
    (comp (ref "R52")
      (value "130 kΩ")
      (footprint "eagle-import:0402_RES")
      (libsource (lib "eagle-import") (part "RESISTOR0402_RES"))
    )
    (comp (ref "R53")
      (value "130 kΩ")
      (footprint "eagle-import:0402_RES")
      (libsource (lib "eagle-import") (part "RESISTOR0402_RES"))
    )
    (comp (ref "R56")
      (value "240 kΩ")
      (footprint "eagle-import:0402_RES")
      (libsource (lib "eagle-import") (part "RESISTOR0402_RES"))
    )
    (comp (ref "R59")
      (value "680 kΩ")
      (footprint "eagle-import:0402_RES")
      (libsource (lib "eagle-import") (part "RESISTOR0402_RES"))
    )
    (comp (ref "R60")
      (value "680 kΩ")
      (footprint "eagle-import:0402_RES")
      (libsource (lib "eagle-import") (part "RESISTOR0402_RES"))
    )
    (comp (ref "R61")
      (value "680 kΩ")
      (footprint "eagle-import:0402_RES")
      (libsource (lib "eagle-import") (part "RESISTOR0402_RES"))
    )
    (comp (ref "R62")
      (value "680 kΩ")
      (footprint "eagle-import:0402_RES")
      (libsource (lib "eagle-import") (part "RESISTOR0402_RES"))
    )
    (comp (ref "R63")
      (value "750 kΩ")
      (footprint "eagle-import:0402_RES")
      (libsource (lib "eagle-import") (part "RESISTOR0402_RES"))
    )
    (comp (ref "U1")
      (value "TLV62130")
      (footprint "eagle-import:TQFN-16_3MM")
      (libsource (lib "eagle-import") (part "TLV62130"))
    )
    (comp (ref "U2")
      (value "TLV62130")
      (footprint "eagle-import:TQFN-16_3MM")
      (libsource (lib "eagle-import") (part "TLV62130"))
    )
    (comp (ref "U3")
      (value "TLV62130")
      (footprint "eagle-import:TQFN-16_3MM")
      (libsource (lib "eagle-import") (part "TLV62130"))
    )
    (comp (ref "U4")
      (value "TLV62130")
      (footprint "eagle-import:TQFN-16_3MM")
      (libsource (lib "eagle-import") (part "TLV62130"))
    )
    (comp (ref "U5")
      (value "TLV62130")
      (footprint "eagle-import:TQFN-16_3MM")
      (libsource (lib "eagle-import") (part "TLV62130"))
    )
    (comp (ref "U20")
      (value "AP22814")
      (footprint "eagle-import:U-DFN2020-6")
      (libsource (lib "eagle-import") (part "AP22814"))
    )
    (comp (ref "U21")
      (value "AP22814")
      (footprint "eagle-import:U-DFN2020-6")
      (libsource (lib "eagle-import") (part "AP22814"))
    )
    (comp (ref "U22")
      (value "AP22814")
      (footprint "eagle-import:U-DFN2020-6")
      (libsource (lib "eagle-import") (part "AP22814"))
    )
    (comp (ref "U23")
      (value "AP22814")
      (footprint "eagle-import:U-DFN2020-6")
      (libsource (lib "eagle-import") (part "AP22814"))
    )
    (comp (ref "U24")
      (value "AP22814")
      (footprint "eagle-import:U-DFN2020-6")
      (libsource (lib "eagle-import") (part "AP22814"))
    )
    (comp (ref "C23")
      (value "0.1 uF")
      (footprint "eagle-import:0402_CAP")
      (libsource (lib "eagle-import") (part "CAPACITOR0402_CAP"))
    )
    (comp (ref "SJ1") (value "SJ") (footprint "eagle-import:SJ") (libsource (lib "eagle-import") (part "SJ")))
    (comp (ref "U29")
      (value "M24C01WMN")
      (footprint "eagle-import:SOIC-8")
      (libsource (lib "eagle-import") (part "M24C01WMN"))
    )
    (comp (ref "C1")
      (value "0.1 uF")
      (footprint "eagle-import:0402_CAP")
      (libsource (lib "eagle-import") (part "CAPACITOR0402_CAP"))
    )
    (comp (ref "C2")
      (value "0.1 uF")
      (footprint "eagle-import:0402_CAP")
      (libsource (lib "eagle-import") (part "CAPACITOR0402_CAP"))
    )
    (comp (ref "C3")
      (value "0.1 uF")
      (footprint "eagle-import:0402_CAP")
      (libsource (lib "eagle-import") (part "CAPACITOR0402_CAP"))
    )
    (comp (ref "C4")
      (value "0.1 uF")
      (footprint "eagle-import:0402_CAP")
      (libsource (lib "eagle-import") (part "CAPACITOR0402_CAP"))
    )
    (comp (ref "R2")
      (value "0.017 Ω")
      (footprint "eagle-import:0805_RES")
      (libsource (lib "eagle-import") (part "RESISTOR0805_RES"))
    )
    (comp (ref "R3")
      (value "0.017 Ω")
      (footprint "eagle-import:0805_RES")
      (libsource (lib "eagle-import") (part "RESISTOR0805_RES"))
    )
    (comp (ref "R4")
      (value "0.017 Ω")
      (footprint "eagle-import:0805_RES")
      (libsource (lib "eagle-import") (part "RESISTOR0805_RES"))
    )
    (comp (ref "R5")
      (value "0.017 Ω")
      (footprint "eagle-import:0805_RES")
      (libsource (lib "eagle-import") (part "RESISTOR0805_RES"))
    )
    (comp (ref "R17")
      (value "2 kΩ")
      (footprint "eagle-import:0402_RES")
      (libsource (lib "eagle-import") (part "RESISTOR0402_RES"))
    )
    (comp (ref "R18")
      (value "2 kΩ")
      (footprint "eagle-import:0402_RES")
      (libsource (lib "eagle-import") (part "RESISTOR0402_RES"))
    )
    (comp (ref "R19")
      (value "2 kΩ")
      (footprint "eagle-import:0402_RES")
      (libsource (lib "eagle-import") (part "RESISTOR0402_RES"))
    )
    (comp (ref "R20")
      (value "2 kΩ")
      (footprint "eagle-import:0402_RES")
      (libsource (lib "eagle-import") (part "RESISTOR0402_RES"))
    )
    (comp (ref "R21")
      (value "2 kΩ")
      (footprint "eagle-import:0402_RES")
      (libsource (lib "eagle-import") (part "RESISTOR0402_RES"))
    )
    (comp (ref "R22")
      (value "2 kΩ")
      (footprint "eagle-import:0402_RES")
      (libsource (lib "eagle-import") (part "RESISTOR0402_RES"))
    )
    (comp (ref "R23")
      (value "2 kΩ")
      (footprint "eagle-import:0402_RES")
      (libsource (lib "eagle-import") (part "RESISTOR0402_RES"))
    )
    (comp (ref "R24")
      (value "2 kΩ")
      (footprint "eagle-import:0402_RES")
      (libsource (lib "eagle-import") (part "RESISTOR0402_RES"))
    )
    (comp (ref "R25")
      (value "2 kΩ")
      (footprint "eagle-import:0402_RES")
      (libsource (lib "eagle-import") (part "RESISTOR0402_RES"))
    )
    (comp (ref "R26")
      (value "2 kΩ")
      (footprint "eagle-import:0402_RES")
      (libsource (lib "eagle-import") (part "RESISTOR0402_RES"))
    )
    (comp (ref "R27")
      (value "2 kΩ")
      (footprint "eagle-import:0402_RES")
      (libsource (lib "eagle-import") (part "RESISTOR0402_RES"))
    )
    (comp (ref "R28")
      (value "2 kΩ")
      (footprint "eagle-import:0402_RES")
      (libsource (lib "eagle-import") (part "RESISTOR0402_RES"))
    )
    (comp (ref "U6")
      (value "PCA9544AQFN-N20")
      (footprint "eagle-import:QFN-N20")
      (libsource (lib "eagle-import") (part "PCA9544AQFN-N20"))
    )
    (comp (ref "U8")
      (value "LTC2941")
      (footprint "eagle-import:DFN-6-2MMX3MM")
      (libsource (lib "eagle-import") (part "LTC2941"))
    )
    (comp (ref "U9")
      (value "LTC2943")
      (footprint "eagle-import:DFN-8")
      (libsource (lib "eagle-import") (part "LTC2943"))
    )
    (comp (ref "U10")
      (value "LTC2943")
      (footprint "eagle-import:DFN-8")
      (libsource (lib "eagle-import") (part "LTC2943"))
    )
    (comp (ref "U11")
      (value "LTC2943")
      (footprint "eagle-import:DFN-8")
      (libsource (lib "eagle-import") (part "LTC2943"))
    )
    (comp (ref "C28")
      (value "1 uF")
      (footprint "eagle-import:0603_CAP")
      (libsource (lib "eagle-import") (part "CAPACITOR0603_CAP"))
    )
    (comp (ref "C39")
      (value "10 uF")
      (footprint "eagle-import:0805_CAP")
      (libsource (lib "eagle-import") (part "CAPACITOR0805_CAP"))
    )
    (comp (ref "C40")
      (value "10 uF")
      (footprint "eagle-import:0805_CAP")
      (libsource (lib "eagle-import") (part "CAPACITOR0805_CAP"))
    )
    (comp (ref "D1")
      (value "DIODE_SCHOTTKYSOT-23F")
      (footprint "eagle-import:SOT-23F")
      (libsource (lib "eagle-import") (part "DIODE_SCHOTTKYSOT-23F"))
    )
    (comp (ref "D2")
      (value "DIODE_ZENERSOT323")
      (footprint "eagle-import:SOD323")
      (libsource (lib "eagle-import") (part "DIODE_ZENERSOT323"))
    )
    (comp (ref "D3")
      (value "DIODE_SCHOTTKYSOD323")
      (footprint "eagle-import:SOD323")
      (libsource (lib "eagle-import") (part "DIODE_SCHOTTKYSOD323"))
    )
    (comp (ref "L6")
      (value "6.8uH")
      (footprint "eagle-import:IHL-2525CZ")
      (libsource (lib "eagle-import") (part "INDUCTORIHL2525CZ"))
    )
    (comp (ref "R10")
      (value "0.05 Ω")
      (footprint "eagle-import:0805_RES")
      (libsource (lib "eagle-import") (part "RESISTOR0805_RES"))
    )
    (comp (ref "R12")
      (value "1 kΩ")
      (footprint "eagle-import:0402_RES")
      (libsource (lib "eagle-import") (part "RESISTOR0402_RES"))
    )
    (comp (ref "R15")
      (value "1 MΩ")
      (footprint "eagle-import:0402_RES")
      (libsource (lib "eagle-import") (part "RESISTOR0402_RES"))
    )
    (comp (ref "R16")
      (value "1 MΩ")
      (footprint "eagle-import:0402_RES")
      (libsource (lib "eagle-import") (part "RESISTOR0402_RES"))
    )
    (comp (ref "R44")
      (value "23.2 kΩ")
      (footprint "eagle-import:0805_RES")
      (libsource (lib "eagle-import") (part "RESISTOR0805_RES"))
    )
    (comp (ref "R57")
      (value "301 kΩ")
      (footprint "eagle-import:0805_RES")
      (libsource (lib "eagle-import") (part "RESISTOR0805_RES"))
    )
    (comp (ref "R58")
      (value "340 kΩ")
      (footprint "eagle-import:0805_RES")
      (libsource (lib "eagle-import") (part "RESISTOR0805_RES"))
    )
    (comp (ref "R64")
      (value "953 kΩ")
      (footprint "eagle-import:0805_RES")
      (libsource (lib "eagle-import") (part "RESISTOR0805_RES"))
    )
    (comp (ref "U16")
      (value "LT3652")
      (footprint "eagle-import:DFN-12_3MM")
      (libsource (lib "eagle-import") (part "LT3652"))
    )
    (comp (ref "U17")
      (value "LM234")
      (footprint "eagle-import:SOIC-8")
      (libsource (lib "eagle-import") (part "LM234"))
    )
    (comp (ref "C5")
      (value "0.1 uF")
      (footprint "eagle-import:0402_CAP")
      (libsource (lib "eagle-import") (part "CAPACITOR0402_CAP"))
    )
    (comp (ref "C6")
      (value "0.1 uF")
      (footprint "eagle-import:0402_CAP")
      (libsource (lib "eagle-import") (part "CAPACITOR0402_CAP"))
    )
    (comp (ref "C7")
      (value "0.1 uF")
      (footprint "eagle-import:0402_CAP")
      (libsource (lib "eagle-import") (part "CAPACITOR0402_CAP"))
    )
    (comp (ref "C8")
      (value "0.1 uF")
      (footprint "eagle-import:0402_CAP")
      (libsource (lib "eagle-import") (part "CAPACITOR0402_CAP"))
    )
    (comp (ref "R6")
      (value "0.017 Ω")
      (footprint "eagle-import:0805_RES")
      (libsource (lib "eagle-import") (part "RESISTOR0805_RES"))
    )
    (comp (ref "R7")
      (value "0.017 Ω")
      (footprint "eagle-import:0805_RES")
      (libsource (lib "eagle-import") (part "RESISTOR0805_RES"))
    )
    (comp (ref "R8")
      (value "0.017 Ω")
      (footprint "eagle-import:0805_RES")
      (libsource (lib "eagle-import") (part "RESISTOR0805_RES"))
    )
    (comp (ref "R9")
      (value "0.017 Ω")
      (footprint "eagle-import:0805_RES")
      (libsource (lib "eagle-import") (part "RESISTOR0805_RES"))
    )
    (comp (ref "R29")
      (value "2 kΩ")
      (footprint "eagle-import:0402_RES")
      (libsource (lib "eagle-import") (part "RESISTOR0402_RES"))
    )
    (comp (ref "R30")
      (value "2 kΩ")
      (footprint "eagle-import:0402_RES")
      (libsource (lib "eagle-import") (part "RESISTOR0402_RES"))
    )
    (comp (ref "R31")
      (value "2 kΩ")
      (footprint "eagle-import:0402_RES")
      (libsource (lib "eagle-import") (part "RESISTOR0402_RES"))
    )
    (comp (ref "R32")
      (value "2 kΩ")
      (footprint "eagle-import:0402_RES")
      (libsource (lib "eagle-import") (part "RESISTOR0402_RES"))
    )
    (comp (ref "R33")
      (value "2 kΩ")
      (footprint "eagle-import:0402_RES")
      (libsource (lib "eagle-import") (part "RESISTOR0402_RES"))
    )
    (comp (ref "R34")
      (value "2 kΩ")
      (footprint "eagle-import:0402_RES")
      (libsource (lib "eagle-import") (part "RESISTOR0402_RES"))
    )
    (comp (ref "R35")
      (value "2 kΩ")
      (footprint "eagle-import:0402_RES")
      (libsource (lib "eagle-import") (part "RESISTOR0402_RES"))
    )
    (comp (ref "R36")
      (value "2 kΩ")
      (footprint "eagle-import:0402_RES")
      (libsource (lib "eagle-import") (part "RESISTOR0402_RES"))
    )
    (comp (ref "R37")
      (value "2 kΩ")
      (footprint "eagle-import:0402_RES")
      (libsource (lib "eagle-import") (part "RESISTOR0402_RES"))
    )
    (comp (ref "R38")
      (value "2 kΩ")
      (footprint "eagle-import:0402_RES")
      (libsource (lib "eagle-import") (part "RESISTOR0402_RES"))
    )
    (comp (ref "R39")
      (value "2 kΩ")
      (footprint "eagle-import:0402_RES")
      (libsource (lib "eagle-import") (part "RESISTOR0402_RES"))
    )
    (comp (ref "R40")
      (value "2 kΩ")
      (footprint "eagle-import:0402_RES")
      (libsource (lib "eagle-import") (part "RESISTOR0402_RES"))
    )
    (comp (ref "U7")
      (value "PCA9544AQFN-N20")
      (footprint "eagle-import:QFN-N20")
      (libsource (lib "eagle-import") (part "PCA9544AQFN-N20"))
    )
    (comp (ref "U12")
      (value "LTC2943")
      (footprint "eagle-import:DFN-8")
      (libsource (lib "eagle-import") (part "LTC2943"))
    )
    (comp (ref "U13")
      (value "LTC2943")
      (footprint "eagle-import:DFN-8")
      (libsource (lib "eagle-import") (part "LTC2943"))
    )
    (comp (ref "U14")
      (value "LTC2943")
      (footprint "eagle-import:DFN-8")
      (libsource (lib "eagle-import") (part "LTC2943"))
    )
    (comp (ref "U15")
      (value "LTC2943")
      (footprint "eagle-import:DFN-8")
      (libsource (lib "eagle-import") (part "LTC2943"))
    )
  )
  (nets
    (net (code "1") (name "CHRG") (class "Default")
      (node (ref "CHRG") (pin "TESTPOINT") (pinfunction "TESTPOINT_TESTPOINT") (pintype "bidirectional"))
      (node (ref "R16") (pin "1") (pinfunction "1_1") (pintype "passive"))
      (node (ref "U16") (pin "4") (pinfunction "~{CHRG}_4") (pintype "bidirectional"))
    )
    (net (code "2") (name "CHRG_FAULT") (class "Default")
      (node (ref "FAULT") (pin "TESTPOINT") (pinfunction "TESTPOINT_TESTPOINT") (pintype "bidirectional"))
      (node (ref "R15") (pin "1") (pinfunction "1_1") (pintype "passive"))
      (node (ref "U16") (pin "5") (pinfunction "~{FAULT}_5") (pintype "bidirectional"))
    )
    (net (code "3") (name "GND") (class "Default")
      (node (ref "C1") (pin "2") (pinfunction "2_2") (pintype "bidirectional"))
      (node (ref "C10") (pin "2") (pinfunction "2_2") (pintype "bidirectional"))
      (node (ref "C11") (pin "2") (pinfunction "2_2") (pintype "bidirectional"))
      (node (ref "C12") (pin "2") (pinfunction "2_2") (pintype "bidirectional"))
      (node (ref "C13") (pin "2") (pinfunction "2_2") (pintype "bidirectional"))
      (node (ref "C15") (pin "2") (pinfunction "2_2") (pintype "bidirectional"))
      (node (ref "C16") (pin "2") (pinfunction "2_2") (pintype "bidirectional"))
      (node (ref "C17") (pin "2") (pinfunction "2_2") (pintype "bidirectional"))
      (node (ref "C18") (pin "2") (pinfunction "2_2") (pintype "bidirectional"))
      (node (ref "C19") (pin "2") (pinfunction "2_2") (pintype "bidirectional"))
      (node (ref "C2") (pin "2") (pinfunction "2_2") (pintype "bidirectional"))
      (node (ref "C20") (pin "2") (pinfunction "2_2") (pintype "bidirectional"))
      (node (ref "C23") (pin "2") (pinfunction "2_2") (pintype "bidirectional"))
      (node (ref "C29") (pin "1") (pinfunction "1_1") (pintype "bidirectional"))
      (node (ref "C3") (pin "2") (pinfunction "2_2") (pintype "bidirectional"))
      (node (ref "C30") (pin "1") (pinfunction "1_1") (pintype "bidirectional"))
      (node (ref "C31") (pin "1") (pinfunction "1_1") (pintype "bidirectional"))
      (node (ref "C32") (pin "1") (pinfunction "1_1") (pintype "bidirectional"))
      (node (ref "C33") (pin "1") (pinfunction "1_1") (pintype "bidirectional"))
      (node (ref "C34") (pin "P$2") (pinfunction "2_P$2") (pintype "bidirectional"))
      (node (ref "C35") (pin "P$2") (pinfunction "2_P$2") (pintype "bidirectional"))
      (node (ref "C36") (pin "P$2") (pinfunction "2_P$2") (pintype "bidirectional"))
      (node (ref "C37") (pin "P$2") (pinfunction "2_P$2") (pintype "bidirectional"))
      (node (ref "C38") (pin "P$2") (pinfunction "2_P$2") (pintype "bidirectional"))
      (node (ref "C4") (pin "2") (pinfunction "2_2") (pintype "bidirectional"))
      (node (ref "C41") (pin "1") (pinfunction "1_1") (pintype "bidirectional"))
      (node (ref "C42") (pin "1") (pinfunction "1_1") (pintype "bidirectional"))
      (node (ref "C43") (pin "1") (pinfunction "1_1") (pintype "bidirectional"))
      (node (ref "C44") (pin "1") (pinfunction "1_1") (pintype "bidirectional"))
      (node (ref "C45") (pin "1") (pinfunction "1_1") (pintype "bidirectional"))
      (node (ref "C46") (pin "1") (pinfunction "1_1") (pintype "bidirectional"))
      (node (ref "C47") (pin "1") (pinfunction "1_1") (pintype "bidirectional"))
      (node (ref "C48") (pin "1") (pinfunction "1_1") (pintype "bidirectional"))
      (node (ref "C49") (pin "1") (pinfunction "1_1") (pintype "bidirectional"))
      (node (ref "C5") (pin "2") (pinfunction "2_2") (pintype "bidirectional"))
      (node (ref "C50") (pin "1") (pinfunction "1_1") (pintype "bidirectional"))
      (node (ref "C6") (pin "2") (pinfunction "2_2") (pintype "bidirectional"))
      (node (ref "C7") (pin "2") (pinfunction "2_2") (pintype "bidirectional"))
      (node (ref "C8") (pin "2") (pinfunction "2_2") (pintype "bidirectional"))
      (node (ref "C9") (pin "2") (pinfunction "2_2") (pintype "bidirectional"))
      (node (ref "H1") (pin "B3,0") (pinfunction "MOUNT_B3,0") (pintype "passive"))
      (node (ref "H2") (pin "B3,0") (pinfunction "MOUNT_B3,0") (pintype "passive"))
      (node (ref "H3") (pin "B3,0") (pinfunction "MOUNT_B3,0") (pintype "passive"))
      (node (ref "H4") (pin "B3,0") (pinfunction "MOUNT_B3,0") (pintype "passive"))
      (node (ref "J1") (pin "1") (pinfunction "GND_1") (pintype "power_in"))
      (node (ref "J3") (pin "3") (pinfunction "GND_3") (pintype "bidirectional"))
      (node (ref "JP1") (pin "1") (pinfunction "1_1") (pintype "passive"))
      (node (ref "Q1") (pin "4") (pinfunction "D_4") (pintype "passive"))
      (node (ref "R50") (pin "1") (pinfunction "1_1") (pintype "passive"))
      (node (ref "R51") (pin "1") (pinfunction "1_1") (pintype "passive"))
      (node (ref "R52") (pin "1") (pinfunction "1_1") (pintype "passive"))
      (node (ref "R53") (pin "1") (pinfunction "1_1") (pintype "passive"))
      (node (ref "R56") (pin "1") (pinfunction "1_1") (pintype "passive"))
      (node (ref "U1") (pin "15") (pinfunction "PGND_15") (pintype "bidirectional"))
      (node (ref "U1") (pin "16") (pinfunction "PGND_16") (pintype "bidirectional"))
      (node (ref "U1") (pin "6") (pinfunction "AGND_6") (pintype "bidirectional"))
      (node (ref "U1") (pin "7") (pinfunction "FSW_7") (pintype "bidirectional"))
      (node (ref "U1") (pin "8") (pinfunction "DEF_8") (pintype "bidirectional"))
      (node (ref "U1") (pin "GND") (pinfunction "PGND_GND") (pintype "bidirectional"))
      (node (ref "U10") (pin "P$1") (pinfunction "GND_P$1") (pintype "open_collector"))
      (node (ref "U10") (pin "P2") (pinfunction "GND_P2") (pintype "open_collector"))
      (node (ref "U10") (pin "P3") (pinfunction "GND_P3") (pintype "open_collector"))
      (node (ref "U10") (pin "P7") (pinfunction "GND_P7") (pintype "open_collector"))
      (node (ref "U11") (pin "P$1") (pinfunction "GND_P$1") (pintype "open_collector"))
      (node (ref "U11") (pin "P2") (pinfunction "GND_P2") (pintype "open_collector"))
      (node (ref "U11") (pin "P3") (pinfunction "GND_P3") (pintype "open_collector"))
      (node (ref "U11") (pin "P7") (pinfunction "GND_P7") (pintype "open_collector"))
      (node (ref "U12") (pin "P$1") (pinfunction "GND_P$1") (pintype "open_collector"))
      (node (ref "U12") (pin "P2") (pinfunction "GND_P2") (pintype "open_collector"))
      (node (ref "U12") (pin "P3") (pinfunction "GND_P3") (pintype "open_collector"))
      (node (ref "U12") (pin "P7") (pinfunction "GND_P7") (pintype "open_collector"))
      (node (ref "U13") (pin "P$1") (pinfunction "GND_P$1") (pintype "open_collector"))
      (node (ref "U13") (pin "P2") (pinfunction "GND_P2") (pintype "open_collector"))
      (node (ref "U13") (pin "P3") (pinfunction "GND_P3") (pintype "open_collector"))
      (node (ref "U13") (pin "P7") (pinfunction "GND_P7") (pintype "open_collector"))
      (node (ref "U14") (pin "P$1") (pinfunction "GND_P$1") (pintype "open_collector"))
      (node (ref "U14") (pin "P2") (pinfunction "GND_P2") (pintype "open_collector"))
      (node (ref "U14") (pin "P3") (pinfunction "GND_P3") (pintype "open_collector"))
      (node (ref "U14") (pin "P7") (pinfunction "GND_P7") (pintype "open_collector"))
      (node (ref "U15") (pin "P$1") (pinfunction "GND_P$1") (pintype "open_collector"))
      (node (ref "U15") (pin "P2") (pinfunction "GND_P2") (pintype "open_collector"))
      (node (ref "U15") (pin "P3") (pinfunction "GND_P3") (pintype "open_collector"))
      (node (ref "U15") (pin "P7") (pinfunction "GND_P7") (pintype "open_collector"))
      (node (ref "U2") (pin "15") (pinfunction "PGND_15") (pintype "bidirectional"))
      (node (ref "U2") (pin "16") (pinfunction "PGND_16") (pintype "bidirectional"))
      (node (ref "U2") (pin "6") (pinfunction "AGND_6") (pintype "bidirectional"))
      (node (ref "U2") (pin "7") (pinfunction "FSW_7") (pintype "bidirectional"))
      (node (ref "U2") (pin "8") (pinfunction "DEF_8") (pintype "bidirectional"))
      (node (ref "U2") (pin "GND") (pinfunction "PGND_GND") (pintype "bidirectional"))
      (node (ref "U20") (pin "2") (pinfunction "GND_2") (pintype "bidirectional"))
      (node (ref "U21") (pin "2") (pinfunction "GND_2") (pintype "bidirectional"))
      (node (ref "U22") (pin "2") (pinfunction "GND_2") (pintype "bidirectional"))
      (node (ref "U23") (pin "2") (pinfunction "GND_2") (pintype "bidirectional"))
      (node (ref "U24") (pin "2") (pinfunction "GND_2") (pintype "bidirectional"))
      (node (ref "U25") (pin "1") (pinfunction "A0_1") (pintype "bidirectional"))
      (node (ref "U25") (pin "10") (pinfunction "GND_10") (pintype "bidirectional"))
      (node (ref "U25") (pin "3") (pinfunction "A2_3") (pintype "bidirectional"))
      (node (ref "U29") (pin "1") (pinfunction "E0_1") (pintype "bidirectional"))
      (node (ref "U29") (pin "2") (pinfunction "E1_2") (pintype "bidirectional"))
      (node (ref "U29") (pin "3") (pinfunction "E2_3") (pintype "bidirectional"))
      (node (ref "U29") (pin "4") (pinfunction "GND_4") (pintype "bidirectional"))
      (node (ref "U3") (pin "15") (pinfunction "PGND_15") (pintype "bidirectional"))
      (node (ref "U3") (pin "16") (pinfunction "PGND_16") (pintype "bidirectional"))
      (node (ref "U3") (pin "6") (pinfunction "AGND_6") (pintype "bidirectional"))
      (node (ref "U3") (pin "7") (pinfunction "FSW_7") (pintype "bidirectional"))
      (node (ref "U3") (pin "8") (pinfunction "DEF_8") (pintype "bidirectional"))
      (node (ref "U3") (pin "GND") (pinfunction "PGND_GND") (pintype "bidirectional"))
      (node (ref "U4") (pin "15") (pinfunction "PGND_15") (pintype "bidirectional"))
      (node (ref "U4") (pin "16") (pinfunction "PGND_16") (pintype "bidirectional"))
      (node (ref "U4") (pin "6") (pinfunction "AGND_6") (pintype "bidirectional"))
      (node (ref "U4") (pin "7") (pinfunction "FSW_7") (pintype "bidirectional"))
      (node (ref "U4") (pin "8") (pinfunction "DEF_8") (pintype "bidirectional"))
      (node (ref "U4") (pin "GND") (pinfunction "PGND_GND") (pintype "bidirectional"))
      (node (ref "U5") (pin "15") (pinfunction "PGND_15") (pintype "bidirectional"))
      (node (ref "U5") (pin "16") (pinfunction "PGND_16") (pintype "bidirectional"))
      (node (ref "U5") (pin "6") (pinfunction "AGND_6") (pintype "bidirectional"))
      (node (ref "U5") (pin "7") (pinfunction "FSW_7") (pintype "bidirectional"))
      (node (ref "U5") (pin "8") (pinfunction "DEF_8") (pintype "bidirectional"))
      (node (ref "U5") (pin "GND") (pinfunction "PGND_GND") (pintype "bidirectional"))
      (node (ref "U6") (pin "1") (pinfunction "A0_1") (pintype "bidirectional"))
      (node (ref "U6") (pin "10") (pinfunction "GND_10") (pintype "bidirectional"))
      (node (ref "U6") (pin "2") (pinfunction "A1_2") (pintype "bidirectional"))
      (node (ref "U6") (pin "3") (pinfunction "A2_3") (pintype "bidirectional"))
      (node (ref "U7") (pin "10") (pinfunction "GND_10") (pintype "bidirectional"))
      (node (ref "U7") (pin "2") (pinfunction "A1_2") (pintype "bidirectional"))
      (node (ref "U7") (pin "3") (pinfunction "A2_3") (pintype "bidirectional"))
      (node (ref "U8") (pin "2") (pinfunction "GND_2") (pintype "open_collector"))
      (node (ref "U9") (pin "P$1") (pinfunction "GND_P$1") (pintype "open_collector"))
      (node (ref "U9") (pin "P2") (pinfunction "GND_P2") (pintype "open_collector"))
      (node (ref "U9") (pin "P3") (pinfunction "GND_P3") (pintype "open_collector"))
      (node (ref "U9") (pin "P7") (pinfunction "GND_P7") (pintype "open_collector"))
    )
    (net (code "4") (name "MONITOR_GND") (class "Default")
      (node (ref "C14") (pin "2") (pinfunction "2_2") (pintype "bidirectional"))
      (node (ref "C21") (pin "2") (pinfunction "2_2") (pintype "bidirectional"))
      (node (ref "C22") (pin "2") (pinfunction "2_2") (pintype "bidirectional"))
      (node (ref "C24") (pin "2") (pinfunction "2_2") (pintype "bidirectional"))
      (node (ref "C25") (pin "2") (pinfunction "2_2") (pintype "bidirectional"))
      (node (ref "C26") (pin "2") (pinfunction "2_2") (pintype "bidirectional"))
      (node (ref "C27") (pin "2") (pinfunction "2_2") (pintype "bidirectional"))
      (node (ref "C39") (pin "P$2") (pinfunction "2_P$2") (pintype "bidirectional"))
      (node (ref "C40") (pin "P$2") (pinfunction "2_P$2") (pintype "bidirectional"))
      (node (ref "D1") (pin "P$1") (pinfunction "ANODE_P$1") (pintype "bidirectional"))
      (node (ref "J1") (pin "20") (pinfunction "VSOL-_20") (pintype "power_in"))
      (node (ref "MON_GND") (pin "TESTPOINT") (pinfunction "TESTPOINT_TESTPOINT") (pintype "bidirectional"))
      (node (ref "Q1") (pin "3") (pinfunction "S_3") (pintype "passive"))
      (node (ref "R1") (pin "2") (pinfunction "2_2") (pintype "passive"))
      (node (ref "R14") (pin "1") (pinfunction "1_1") (pintype "passive"))
      (node (ref "R44") (pin "1") (pinfunction "1_1") (pintype "passive"))
      (node (ref "R58") (pin "2") (pinfunction "2_2") (pintype "passive"))
      (node (ref "RESET") (pin "3") (pinfunction "P$2_3") (pintype "passive"))
      (node (ref "RESET") (pin "4") (pinfunction "P$2_4") (pintype "passive"))
      (node (ref "S1") (pin "1") (pinfunction "A_1") (pintype "bidirectional"))
      (node (ref "U16") (pin "13") (pinfunction "GND_13") (pintype "bidirectional"))
      (node (ref "U16") (pin "6") (pinfunction "TIMER_6") (pintype "bidirectional"))
      (node (ref "U18") (pin "13") (pinfunction "CELLX_13") (pintype "bidirectional"))
      (node (ref "U18") (pin "15") (pinfunction "CSN_15") (pintype "bidirectional"))
      (node (ref "U18") (pin "4") (pinfunction "CSN_4") (pintype "bidirectional"))
      (node (ref "U18") (pin "6") (pinfunction "CELL2_6") (pintype "bidirectional"))
      (node (ref "U18") (pin "7") (pinfunction "CELL1_7") (pintype "bidirectional"))
      (node (ref "U19") (pin "P$1") (pinfunction "GND_P$1") (pintype "bidirectional"))
      (node (ref "U26") (pin "P$1") (pinfunction "GND_P$1") (pintype "open_collector"))
      (node (ref "U26") (pin "P2") (pinfunction "GND_P2") (pintype "open_collector"))
      (node (ref "U26") (pin "P3") (pinfunction "GND_P3") (pintype "open_collector"))
      (node (ref "U26") (pin "P7") (pinfunction "GND_P7") (pintype "open_collector"))
      (node (ref "U27") (pin "4") (pinfunction "GND_4") (pintype "bidirectional"))
      (node (ref "U28") (pin "3") (pinfunction "GND_3") (pintype "bidirectional"))
    )
    (net (code "5") (name "Net-(D1-CATHODE)") (class "Default")
      (node (ref "C28") (pin "1") (pinfunction "1_1") (pintype "bidirectional"))
      (node (ref "D1") (pin "P$3") (pinfunction "CATHODE_P$3") (pintype "bidirectional"))
      (node (ref "L6") (pin "P$1") (pinfunction "1_P$1") (pintype "bidirectional"))
      (node (ref "U16") (pin "12") (pinfunction "SW_12") (pintype "bidirectional"))
    )
    (net (code "6") (name "Net-(D2-ANODE)") (class "Default")
      (node (ref "D2") (pin "P$2") (pinfunction "ANODE_P$2") (pintype "bidirectional"))
      (node (ref "D3") (pin "P$2") (pinfunction "ANODE_P$2") (pintype "bidirectional"))
    )
    (net (code "7") (name "Net-(D3-CATHODE)") (class "Default")
      (node (ref "C28") (pin "2") (pinfunction "2_2") (pintype "bidirectional"))
      (node (ref "D3") (pin "P$1") (pinfunction "CATHODE_P$1") (pintype "bidirectional"))
      (node (ref "U16") (pin "11") (pinfunction "BOOST_11") (pintype "bidirectional"))
    )
    (net (code "8") (name "Net-(L1-1)") (class "Default")
      (node (ref "L1") (pin "P$1") (pinfunction "1_P$1") (pintype "bidirectional"))
      (node (ref "U1") (pin "1") (pinfunction "SW_1") (pintype "bidirectional"))
      (node (ref "U1") (pin "2") (pinfunction "SW_2") (pintype "bidirectional"))
      (node (ref "U1") (pin "3") (pinfunction "SW_3") (pintype "bidirectional"))
    )
    (net (code "9") (name "Net-(L1-2)") (class "Default")
      (node (ref "C42") (pin "2") (pinfunction "2_2") (pintype "bidirectional"))
      (node (ref "L1") (pin "P$2") (pinfunction "2_P$2") (pintype "bidirectional"))
      (node (ref "R46") (pin "2") (pinfunction "2_2") (pintype "passive"))
      (node (ref "R59") (pin "2") (pinfunction "2_2") (pintype "passive"))
      (node (ref "U1") (pin "14") (pinfunction "VOS_14") (pintype "bidirectional"))
      (node (ref "U21") (pin "1") (pinfunction "IN_1") (pintype "bidirectional"))
      (node (ref "U21") (pin "3") (pinfunction "EN_3") (pintype "bidirectional"))
    )
    (net (code "10") (name "Net-(L2-1)") (class "Default")
      (node (ref "L2") (pin "P$1") (pinfunction "1_P$1") (pintype "bidirectional"))
      (node (ref "U2") (pin "1") (pinfunction "SW_1") (pintype "bidirectional"))
      (node (ref "U2") (pin "2") (pinfunction "SW_2") (pintype "bidirectional"))
      (node (ref "U2") (pin "3") (pinfunction "SW_3") (pintype "bidirectional"))
    )
    (net (code "11") (name "Net-(L2-2)") (class "Default")
      (node (ref "C43") (pin "2") (pinfunction "2_2") (pintype "bidirectional"))
      (node (ref "L2") (pin "P$2") (pinfunction "2_P$2") (pintype "bidirectional"))
      (node (ref "R47") (pin "2") (pinfunction "2_2") (pintype "passive"))
      (node (ref "R60") (pin "2") (pinfunction "2_2") (pintype "passive"))
      (node (ref "U2") (pin "14") (pinfunction "VOS_14") (pintype "bidirectional"))
      (node (ref "U22") (pin "1") (pinfunction "IN_1") (pintype "bidirectional"))
      (node (ref "U22") (pin "3") (pinfunction "EN_3") (pintype "bidirectional"))
    )
    (net (code "12") (name "Net-(L3-1)") (class "Default")
      (node (ref "L3") (pin "P$1") (pinfunction "1_P$1") (pintype "bidirectional"))
      (node (ref "U3") (pin "1") (pinfunction "SW_1") (pintype "bidirectional"))
      (node (ref "U3") (pin "2") (pinfunction "SW_2") (pintype "bidirectional"))
      (node (ref "U3") (pin "3") (pinfunction "SW_3") (pintype "bidirectional"))
    )
    (net (code "13") (name "Net-(L3-2)") (class "Default")
      (node (ref "C44") (pin "2") (pinfunction "2_2") (pintype "bidirectional"))
      (node (ref "L3") (pin "P$2") (pinfunction "2_P$2") (pintype "bidirectional"))
      (node (ref "R48") (pin "2") (pinfunction "2_2") (pintype "passive"))
      (node (ref "R61") (pin "2") (pinfunction "2_2") (pintype "passive"))
      (node (ref "U23") (pin "1") (pinfunction "IN_1") (pintype "bidirectional"))
      (node (ref "U23") (pin "3") (pinfunction "EN_3") (pintype "bidirectional"))
      (node (ref "U3") (pin "14") (pinfunction "VOS_14") (pintype "bidirectional"))
    )
    (net (code "14") (name "Net-(L4-1)") (class "Default")
      (node (ref "L4") (pin "P$1") (pinfunction "1_P$1") (pintype "bidirectional"))
      (node (ref "U4") (pin "1") (pinfunction "SW_1") (pintype "bidirectional"))
      (node (ref "U4") (pin "2") (pinfunction "SW_2") (pintype "bidirectional"))
      (node (ref "U4") (pin "3") (pinfunction "SW_3") (pintype "bidirectional"))
    )
    (net (code "15") (name "Net-(L4-2)") (class "Default")
      (node (ref "C41") (pin "2") (pinfunction "2_2") (pintype "bidirectional"))
      (node (ref "L4") (pin "P$2") (pinfunction "2_P$2") (pintype "bidirectional"))
      (node (ref "R45") (pin "2") (pinfunction "2_2") (pintype "passive"))
      (node (ref "R63") (pin "2") (pinfunction "2_2") (pintype "passive"))
      (node (ref "U20") (pin "1") (pinfunction "IN_1") (pintype "bidirectional"))
      (node (ref "U20") (pin "3") (pinfunction "EN_3") (pintype "bidirectional"))
      (node (ref "U4") (pin "14") (pinfunction "VOS_14") (pintype "bidirectional"))
    )
    (net (code "16") (name "Net-(L5-1)") (class "Default")
      (node (ref "L5") (pin "P$1") (pinfunction "1_P$1") (pintype "bidirectional"))
      (node (ref "U5") (pin "1") (pinfunction "SW_1") (pintype "bidirectional"))
      (node (ref "U5") (pin "2") (pinfunction "SW_2") (pintype "bidirectional"))
      (node (ref "U5") (pin "3") (pinfunction "SW_3") (pintype "bidirectional"))
    )
    (net (code "17") (name "Net-(L5-2)") (class "Default")
      (node (ref "C45") (pin "2") (pinfunction "2_2") (pintype "bidirectional"))
      (node (ref "L5") (pin "P$2") (pinfunction "2_P$2") (pintype "bidirectional"))
      (node (ref "R49") (pin "2") (pinfunction "2_2") (pintype "passive"))
      (node (ref "R62") (pin "2") (pinfunction "2_2") (pintype "passive"))
      (node (ref "U24") (pin "1") (pinfunction "IN_1") (pintype "bidirectional"))
      (node (ref "U24") (pin "3") (pinfunction "EN_3") (pintype "bidirectional"))
      (node (ref "U5") (pin "14") (pinfunction "VOS_14") (pintype "bidirectional"))
    )
    (net (code "18") (name "Net-(L6-2)") (class "Default")
      (node (ref "L6") (pin "P$2") (pinfunction "2_P$2") (pintype "bidirectional"))
      (node (ref "R10") (pin "1") (pinfunction "1_1") (pintype "passive"))
      (node (ref "U16") (pin "10") (pinfunction "SENSE_10") (pintype "bidirectional"))
    )
    (net (code "19") (name "Net-(Q1-G)") (class "Default")
      (node (ref "Q1") (pin "1") (pinfunction "G_1") (pintype "passive"))
      (node (ref "R14") (pin "2") (pinfunction "2_2") (pintype "passive"))
      (node (ref "U27") (pin "7") (pinfunction "~{RESET}_7") (pintype "bidirectional"))
    )
    (net (code "20") (name "Net-(S1-B)") (class "Default")
      (node (ref "C26") (pin "1") (pinfunction "1_1") (pintype "bidirectional"))
      (node (ref "S1") (pin "2") (pinfunction "B_2") (pintype "bidirectional"))
    )
    (net (code "21") (name "Net-(U1-FB)") (class "Default")
      (node (ref "R50") (pin "2") (pinfunction "2_2") (pintype "passive"))
      (node (ref "R59") (pin "1") (pinfunction "1_1") (pintype "passive"))
      (node (ref "U1") (pin "5") (pinfunction "FB_5") (pintype "bidirectional"))
    )
    (net (code "22") (name "Net-(U1-PG)") (class "Default")
      (node (ref "R46") (pin "1") (pinfunction "1_1") (pintype "passive"))
      (node (ref "U1") (pin "4") (pinfunction "PG_4") (pintype "bidirectional"))
    )
    (net (code "23") (name "Net-(U1-SS{slash}TR)") (class "Default")
      (node (ref "C30") (pin "2") (pinfunction "2_2") (pintype "bidirectional"))
      (node (ref "U1") (pin "9") (pinfunction "SS/TR_9") (pintype "bidirectional"))
    )
    (net (code "24") (name "Net-(U2-FB)") (class "Default")
      (node (ref "R51") (pin "2") (pinfunction "2_2") (pintype "passive"))
      (node (ref "R60") (pin "1") (pinfunction "1_1") (pintype "passive"))
      (node (ref "U2") (pin "5") (pinfunction "FB_5") (pintype "bidirectional"))
    )
    (net (code "25") (name "Net-(U2-PG)") (class "Default")
      (node (ref "R47") (pin "1") (pinfunction "1_1") (pintype "passive"))
      (node (ref "U2") (pin "4") (pinfunction "PG_4") (pintype "bidirectional"))
    )
    (net (code "26") (name "Net-(U2-SS{slash}TR)") (class "Default")
      (node (ref "C31") (pin "2") (pinfunction "2_2") (pintype "bidirectional"))
      (node (ref "U2") (pin "9") (pinfunction "SS/TR_9") (pintype "bidirectional"))
    )
    (net (code "27") (name "Net-(U3-FB)") (class "Default")
      (node (ref "R52") (pin "2") (pinfunction "2_2") (pintype "passive"))
      (node (ref "R61") (pin "1") (pinfunction "1_1") (pintype "passive"))
      (node (ref "U3") (pin "5") (pinfunction "FB_5") (pintype "bidirectional"))
    )
    (net (code "28") (name "Net-(U3-PG)") (class "Default")
      (node (ref "R48") (pin "1") (pinfunction "1_1") (pintype "passive"))
      (node (ref "U3") (pin "4") (pinfunction "PG_4") (pintype "bidirectional"))
    )
    (net (code "29") (name "Net-(U3-SS{slash}TR)") (class "Default")
      (node (ref "C32") (pin "2") (pinfunction "2_2") (pintype "bidirectional"))
      (node (ref "U3") (pin "9") (pinfunction "SS/TR_9") (pintype "bidirectional"))
    )
    (net (code "30") (name "Net-(U4-FB)") (class "Default")
      (node (ref "R56") (pin "2") (pinfunction "2_2") (pintype "passive"))
      (node (ref "R63") (pin "1") (pinfunction "1_1") (pintype "passive"))
      (node (ref "U4") (pin "5") (pinfunction "FB_5") (pintype "bidirectional"))
    )
    (net (code "31") (name "Net-(U4-PG)") (class "Default")
      (node (ref "R45") (pin "1") (pinfunction "1_1") (pintype "passive"))
      (node (ref "U4") (pin "4") (pinfunction "PG_4") (pintype "bidirectional"))
    )
    (net (code "32") (name "Net-(U4-SS{slash}TR)") (class "Default")
      (node (ref "C29") (pin "2") (pinfunction "2_2") (pintype "bidirectional"))
      (node (ref "U4") (pin "9") (pinfunction "SS/TR_9") (pintype "bidirectional"))
    )
    (net (code "33") (name "Net-(U5-FB)") (class "Default")
      (node (ref "R53") (pin "2") (pinfunction "2_2") (pintype "passive"))
      (node (ref "R62") (pin "1") (pinfunction "1_1") (pintype "passive"))
      (node (ref "U5") (pin "5") (pinfunction "FB_5") (pintype "bidirectional"))
    )
    (net (code "34") (name "Net-(U5-PG)") (class "Default")
      (node (ref "R49") (pin "1") (pinfunction "1_1") (pintype "passive"))
      (node (ref "U5") (pin "4") (pinfunction "PG_4") (pintype "bidirectional"))
    )
    (net (code "35") (name "Net-(U5-SS{slash}TR)") (class "Default")
      (node (ref "C33") (pin "2") (pinfunction "2_2") (pintype "bidirectional"))
      (node (ref "U5") (pin "9") (pinfunction "SS/TR_9") (pintype "bidirectional"))
    )
    (net (code "36") (name "Net-(U6-SC0)") (class "Default")
      (node (ref "R18") (pin "1") (pinfunction "1_1") (pintype "passive"))
      (node (ref "U6") (pin "6") (pinfunction "SC0_6") (pintype "bidirectional"))
      (node (ref "U8") (pin "3") (pinfunction "SCL_3") (pintype "open_collector"))
    )
    (net (code "37") (name "Net-(U6-SC1)") (class "Default")
      (node (ref "R21") (pin "1") (pinfunction "1_1") (pintype "passive"))
      (node (ref "U6") (pin "9") (pinfunction "SC1_9") (pintype "bidirectional"))
      (node (ref "U9") (pin "P4") (pinfunction "SCL_P4") (pintype "open_collector"))
    )
    (net (code "38") (name "Net-(U6-SD0)") (class "Default")
      (node (ref "R17") (pin "1") (pinfunction "1_1") (pintype "passive"))
      (node (ref "U6") (pin "5") (pinfunction "SD0_5") (pintype "bidirectional"))
      (node (ref "U8") (pin "4") (pinfunction "SDA_4") (pintype "open_collector"))
    )
    (net (code "39") (name "Net-(U6-SD1)") (class "Default")
      (node (ref "R20") (pin "1") (pinfunction "1_1") (pintype "passive"))
      (node (ref "U6") (pin "8") (pinfunction "SD1_8") (pintype "bidirectional"))
      (node (ref "U9") (pin "P5") (pinfunction "SDA_P5") (pintype "open_collector"))
    )
    (net (code "40") (name "Net-(U6-~{INT0})") (class "Default")
      (node (ref "R19") (pin "1") (pinfunction "1_1") (pintype "passive"))
      (node (ref "U6") (pin "4") (pinfunction "~{INT0}_4") (pintype "bidirectional"))
      (node (ref "U8") (pin "5") (pinfunction "~{ALERT}_5") (pintype "open_collector"))
    )
    (net (code "41") (name "Net-(U6-~{INT1})") (class "Default")
      (node (ref "R22") (pin "1") (pinfunction "1_1") (pintype "passive"))
      (node (ref "U6") (pin "7") (pinfunction "~{INT1}_7") (pintype "bidirectional"))
      (node (ref "U9") (pin "P6") (pinfunction "~{ALERT}_P6") (pintype "open_collector"))
    )
    (net (code "42") (name "Net-(U10-SCL)") (class "Default")
      (node (ref "R24") (pin "1") (pinfunction "1_1") (pintype "passive"))
      (node (ref "U10") (pin "P4") (pinfunction "SCL_P4") (pintype "open_collector"))
      (node (ref "U6") (pin "13") (pinfunction "SC2_13") (pintype "bidirectional"))
    )
    (net (code "43") (name "Net-(U10-SDA)") (class "Default")
      (node (ref "R23") (pin "1") (pinfunction "1_1") (pintype "passive"))
      (node (ref "U10") (pin "P5") (pinfunction "SDA_P5") (pintype "open_collector"))
      (node (ref "U6") (pin "12") (pinfunction "SD2_12") (pintype "bidirectional"))
    )
    (net (code "44") (name "Net-(U10-~{ALERT})") (class "Default")
      (node (ref "R25") (pin "1") (pinfunction "1_1") (pintype "passive"))
      (node (ref "U10") (pin "P6") (pinfunction "~{ALERT}_P6") (pintype "open_collector"))
      (node (ref "U6") (pin "11") (pinfunction "~{INT2}_11") (pintype "bidirectional"))
    )
    (net (code "45") (name "Net-(U11-SCL)") (class "Default")
      (node (ref "R27") (pin "1") (pinfunction "1_1") (pintype "passive"))
      (node (ref "U11") (pin "P4") (pinfunction "SCL_P4") (pintype "open_collector"))
      (node (ref "U6") (pin "16") (pinfunction "SC3_16") (pintype "bidirectional"))
    )
    (net (code "46") (name "Net-(U11-SDA)") (class "Default")
      (node (ref "R26") (pin "1") (pinfunction "1_1") (pintype "passive"))
      (node (ref "U11") (pin "P5") (pinfunction "SDA_P5") (pintype "open_collector"))
      (node (ref "U6") (pin "15") (pinfunction "SD3_15") (pintype "bidirectional"))
    )
    (net (code "47") (name "Net-(U11-~{ALERT})") (class "Default")
      (node (ref "R28") (pin "1") (pinfunction "1_1") (pintype "passive"))
      (node (ref "U11") (pin "P6") (pinfunction "~{ALERT}_P6") (pintype "open_collector"))
      (node (ref "U6") (pin "14") (pinfunction "~{INT3}_14") (pintype "bidirectional"))
    )
    (net (code "48") (name "Net-(U12-SCL)") (class "Default")
      (node (ref "R36") (pin "1") (pinfunction "1_1") (pintype "passive"))
      (node (ref "U12") (pin "P4") (pinfunction "SCL_P4") (pintype "open_collector"))
      (node (ref "U7") (pin "6") (pinfunction "SC0_6") (pintype "bidirectional"))
    )
    (net (code "49") (name "Net-(U12-SDA)") (class "Default")
      (node (ref "R35") (pin "1") (pinfunction "1_1") (pintype "passive"))
      (node (ref "U12") (pin "P5") (pinfunction "SDA_P5") (pintype "open_collector"))
      (node (ref "U7") (pin "5") (pinfunction "SD0_5") (pintype "bidirectional"))
    )
    (net (code "50") (name "Net-(U12-~{ALERT})") (class "Default")
      (node (ref "R37") (pin "1") (pinfunction "1_1") (pintype "passive"))
      (node (ref "U12") (pin "P6") (pinfunction "~{ALERT}_P6") (pintype "open_collector"))
      (node (ref "U7") (pin "4") (pinfunction "~{INT0}_4") (pintype "bidirectional"))
    )
    (net (code "51") (name "Net-(U13-SCL)") (class "Default")
      (node (ref "R33") (pin "1") (pinfunction "1_1") (pintype "passive"))
      (node (ref "U13") (pin "P4") (pinfunction "SCL_P4") (pintype "open_collector"))
      (node (ref "U7") (pin "9") (pinfunction "SC1_9") (pintype "bidirectional"))
    )
    (net (code "52") (name "Net-(U13-SDA)") (class "Default")
      (node (ref "R32") (pin "1") (pinfunction "1_1") (pintype "passive"))
      (node (ref "U13") (pin "P5") (pinfunction "SDA_P5") (pintype "open_collector"))
      (node (ref "U7") (pin "8") (pinfunction "SD1_8") (pintype "bidirectional"))
    )
    (net (code "53") (name "Net-(U13-~{ALERT})") (class "Default")
      (node (ref "R34") (pin "1") (pinfunction "1_1") (pintype "passive"))
      (node (ref "U13") (pin "P6") (pinfunction "~{ALERT}_P6") (pintype "open_collector"))
      (node (ref "U7") (pin "7") (pinfunction "~{INT1}_7") (pintype "bidirectional"))
    )
    (net (code "54") (name "Net-(U14-SCL)") (class "Default")
      (node (ref "R30") (pin "1") (pinfunction "1_1") (pintype "passive"))
      (node (ref "U14") (pin "P4") (pinfunction "SCL_P4") (pintype "open_collector"))
      (node (ref "U7") (pin "13") (pinfunction "SC2_13") (pintype "bidirectional"))
    )
    (net (code "55") (name "Net-(U14-SDA)") (class "Default")
      (node (ref "R29") (pin "1") (pinfunction "1_1") (pintype "passive"))
      (node (ref "U14") (pin "P5") (pinfunction "SDA_P5") (pintype "open_collector"))
      (node (ref "U7") (pin "12") (pinfunction "SD2_12") (pintype "bidirectional"))
    )
    (net (code "56") (name "Net-(U14-~{ALERT})") (class "Default")
      (node (ref "R31") (pin "1") (pinfunction "1_1") (pintype "passive"))
      (node (ref "U14") (pin "P6") (pinfunction "~{ALERT}_P6") (pintype "open_collector"))
      (node (ref "U7") (pin "11") (pinfunction "~{INT2}_11") (pintype "bidirectional"))
    )
    (net (code "57") (name "Net-(U15-SCL)") (class "Default")
      (node (ref "R39") (pin "1") (pinfunction "1_1") (pintype "passive"))
      (node (ref "U15") (pin "P4") (pinfunction "SCL_P4") (pintype "open_collector"))
      (node (ref "U7") (pin "16") (pinfunction "SC3_16") (pintype "bidirectional"))
    )
    (net (code "58") (name "Net-(U15-SDA)") (class "Default")
      (node (ref "R38") (pin "1") (pinfunction "1_1") (pintype "passive"))
      (node (ref "U15") (pin "P5") (pinfunction "SDA_P5") (pintype "open_collector"))
      (node (ref "U7") (pin "15") (pinfunction "SD3_15") (pintype "bidirectional"))
    )
    (net (code "59") (name "Net-(U15-~{ALERT})") (class "Default")
      (node (ref "R40") (pin "1") (pinfunction "1_1") (pintype "passive"))
      (node (ref "U15") (pin "P6") (pinfunction "~{ALERT}_P6") (pintype "open_collector"))
      (node (ref "U7") (pin "14") (pinfunction "~{INT3}_14") (pintype "bidirectional"))
    )
    (net (code "60") (name "Net-(U16-VFB)") (class "Default")
      (node (ref "R58") (pin "1") (pinfunction "1_1") (pintype "passive"))
      (node (ref "R64") (pin "1") (pinfunction "1_1") (pintype "passive"))
      (node (ref "U16") (pin "7") (pinfunction "VFB_7") (pintype "bidirectional"))
    )
    (net (code "61") (name "Net-(U16-VIN_REG)") (class "Default")
      (node (ref "R12") (pin "1") (pinfunction "1_1") (pintype "passive"))
      (node (ref "R44") (pin "2") (pinfunction "2_2") (pintype "passive"))
      (node (ref "R57") (pin "1") (pinfunction "1_1") (pintype "passive"))
      (node (ref "U16") (pin "2") (pinfunction "VIN_REG_2") (pintype "bidirectional"))
      (node (ref "U17") (pin "6") (pinfunction "V-_6") (pintype "bidirectional"))
    )
    (net (code "62") (name "Net-(U17-R)") (class "Default")
      (node (ref "R12") (pin "2") (pinfunction "2_2") (pintype "passive"))
      (node (ref "U17") (pin "1") (pinfunction "R_1") (pintype "bidirectional"))
    )
    (net (code "63") (name "Net-(U18-ALRT1)") (class "Default")
      (node (ref "R13") (pin "1") (pinfunction "1_1") (pintype "passive"))
      (node (ref "U18") (pin "8") (pinfunction "ALRT1_8") (pintype "bidirectional"))
      (node (ref "U19") (pin "P$6") (pinfunction "VUSB_P$6") (pintype "bidirectional"))
    )
    (net (code "64") (name "Net-(U18-REG2)") (class "Default")
      (node (ref "C24") (pin "1") (pinfunction "1_1") (pintype "bidirectional"))
      (node (ref "U18") (pin "3") (pinfunction "REG2_3") (pintype "bidirectional"))
    )
    (net (code "65") (name "Net-(U18-REG3)") (class "Default")
      (node (ref "C25") (pin "1") (pinfunction "1_1") (pintype "bidirectional"))
      (node (ref "U18") (pin "1") (pinfunction "REG3_1") (pintype "bidirectional"))
    )
    (net (code "66") (name "Net-(U18-SCL)") (class "Default")
      (node (ref "R55") (pin "1") (pinfunction "1_1") (pintype "passive"))
      (node (ref "U18") (pin "11") (pinfunction "SCL_11") (pintype "bidirectional"))
      (node (ref "U19") (pin "P$5") (pinfunction "D+_P$5") (pintype "bidirectional"))
    )
    (net (code "67") (name "Net-(U18-SDA)") (class "Default")
      (node (ref "R54") (pin "1") (pinfunction "1_1") (pintype "passive"))
      (node (ref "U18") (pin "12") (pinfunction "SDA_12") (pintype "bidirectional"))
      (node (ref "U19") (pin "P$4") (pinfunction "D-_P$4") (pintype "bidirectional"))
    )
    (net (code "68") (name "Net-(U25-SC0)") (class "Default")
      (node (ref "R42") (pin "1") (pinfunction "1_1") (pintype "passive"))
      (node (ref "U25") (pin "6") (pinfunction "SC0_6") (pintype "bidirectional"))
      (node (ref "U26") (pin "P4") (pinfunction "SCL_P4") (pintype "open_collector"))
    )
    (net (code "69") (name "Net-(U25-SD0)") (class "Default")
      (node (ref "R41") (pin "1") (pinfunction "1_1") (pintype "passive"))
      (node (ref "U25") (pin "5") (pinfunction "SD0_5") (pintype "bidirectional"))
      (node (ref "U26") (pin "P5") (pinfunction "SDA_P5") (pintype "open_collector"))
    )
    (net (code "70") (name "Net-(U25-~{INT0})") (class "Default")
      (node (ref "R43") (pin "1") (pinfunction "1_1") (pintype "passive"))
      (node (ref "U25") (pin "4") (pinfunction "~{INT0}_4") (pintype "bidirectional"))
      (node (ref "U26") (pin "P6") (pinfunction "~{ALERT}_P6") (pintype "open_collector"))
    )
    (net (code "71") (name "Net-(U27-SRT)") (class "Default")
      (node (ref "C27") (pin "1") (pinfunction "1_1") (pintype "bidirectional"))
      (node (ref "U27") (pin "3") (pinfunction "SRT_3") (pintype "bidirectional"))
    )
    (net (code "72") (name "Net-(U27-SWT)") (class "Default")
      (node (ref "S1") (pin "IN") (pinfunction "IN_IN") (pintype "bidirectional"))
      (node (ref "U27") (pin "2") (pinfunction "SWT_2") (pintype "bidirectional"))
    )
    (net (code "73") (name "Net-(U27-VCC)") (class "Default")
      (node (ref "C22") (pin "1") (pinfunction "1_1") (pintype "bidirectional"))
      (node (ref "U27") (pin "5") (pinfunction "WDS_5") (pintype "bidirectional"))
      (node (ref "U27") (pin "8") (pinfunction "VCC_8") (pintype "bidirectional"))
      (node (ref "U28") (pin "1") (pinfunction "OUT_1") (pintype "bidirectional"))
    )
    (net (code "74") (name "Net-(U27-~{MR})") (class "Default")
      (node (ref "RESET") (pin "1") (pinfunction "P$1_1") (pintype "passive"))
      (node (ref "RESET") (pin "2") (pinfunction "P$1_2") (pintype "passive"))
      (node (ref "U27") (pin "1") (pinfunction "~{MR}_1") (pintype "bidirectional"))
    )
    (net (code "75") (name "Net-(U29-~{WC})") (class "Default")
      (node (ref "SJ1") (pin "2") (pinfunction "2_2") (pintype "passive"))
      (node (ref "U29") (pin "7") (pinfunction "~{WC}_7") (pintype "bidirectional"))
    )
    (net (code "76") (name "SCL") (class "Default")
      (node (ref "J1") (pin "5") (pinfunction "SMBCLK_5") (pintype "open_collector"))
      (node (ref "J3") (pin "1") (pinfunction "SCL_1") (pintype "bidirectional"))
      (node (ref "R55") (pin "2") (pinfunction "2_2") (pintype "passive"))
      (node (ref "U25") (pin "18") (pinfunction "SCL_18") (pintype "bidirectional"))
      (node (ref "U29") (pin "6") (pinfunction "SCL_6") (pintype "bidirectional"))
      (node (ref "U6") (pin "18") (pinfunction "SCL_18") (pintype "bidirectional"))
      (node (ref "U7") (pin "18") (pinfunction "SCL_18") (pintype "bidirectional"))
    )
    (net (code "77") (name "SDA") (class "Default")
      (node (ref "J1") (pin "3") (pinfunction "SMBDATA_3") (pintype "open_collector"))
      (node (ref "J3") (pin "5") (pinfunction "SDA_5") (pintype "bidirectional"))
      (node (ref "R54") (pin "2") (pinfunction "2_2") (pintype "passive"))
      (node (ref "U25") (pin "19") (pinfunction "SDA_19") (pintype "bidirectional"))
      (node (ref "U29") (pin "5") (pinfunction "SDA_5") (pintype "bidirectional"))
      (node (ref "U6") (pin "19") (pinfunction "SDA_19") (pintype "bidirectional"))
      (node (ref "U7") (pin "19") (pinfunction "SDA_19") (pintype "bidirectional"))
    )
    (net (code "78") (name "VBAT+") (class "Default")
      (node (ref "C10") (pin "1") (pinfunction "1_1") (pintype "bidirectional"))
      (node (ref "C11") (pin "1") (pinfunction "1_1") (pintype "bidirectional"))
      (node (ref "C12") (pin "1") (pinfunction "1_1") (pintype "bidirectional"))
      (node (ref "C13") (pin "1") (pinfunction "1_1") (pintype "bidirectional"))
      (node (ref "C14") (pin "1") (pinfunction "1_1") (pintype "bidirectional"))
      (node (ref "C21") (pin "1") (pinfunction "1_1") (pintype "bidirectional"))
      (node (ref "C34") (pin "P$1") (pinfunction "1_P$1") (pintype "bidirectional"))
      (node (ref "C35") (pin "P$1") (pinfunction "1_P$1") (pintype "bidirectional"))
      (node (ref "C36") (pin "P$1") (pinfunction "1_P$1") (pintype "bidirectional"))
      (node (ref "C37") (pin "P$1") (pinfunction "1_P$1") (pintype "bidirectional"))
      (node (ref "C38") (pin "P$1") (pinfunction "1_P$1") (pintype "bidirectional"))
      (node (ref "C39") (pin "P$1") (pinfunction "1_P$1") (pintype "bidirectional"))
      (node (ref "C9") (pin "1") (pinfunction "1_1") (pintype "bidirectional"))
      (node (ref "D2") (pin "P$1") (pinfunction "CATHODE_P$1") (pintype "bidirectional"))
      (node (ref "J1") (pin "17") (pinfunction "VBATT+_17") (pintype "power_in"))
      (node (ref "JP1") (pin "4") (pinfunction "4_4") (pintype "passive"))
      (node (ref "R10") (pin "2") (pinfunction "2_2") (pintype "passive"))
      (node (ref "R64") (pin "2") (pinfunction "2_2") (pintype "passive"))
      (node (ref "U1") (pin "10") (pinfunction "AVIN_10") (pintype "bidirectional"))
      (node (ref "U1") (pin "11") (pinfunction "PVIN_11") (pintype "bidirectional"))
      (node (ref "U1") (pin "12") (pinfunction "PVIN_12") (pintype "bidirectional"))
      (node (ref "U1") (pin "13") (pinfunction "EN_13") (pintype "bidirectional"))
      (node (ref "U16") (pin "9") (pinfunction "BAT_9") (pintype "bidirectional"))
      (node (ref "U18") (pin "5") (pinfunction "VBATT_5") (pintype "bidirectional"))
      (node (ref "U2") (pin "10") (pinfunction "AVIN_10") (pintype "bidirectional"))
      (node (ref "U2") (pin "11") (pinfunction "PVIN_11") (pintype "bidirectional"))
      (node (ref "U2") (pin "12") (pinfunction "PVIN_12") (pintype "bidirectional"))
      (node (ref "U2") (pin "13") (pinfunction "EN_13") (pintype "bidirectional"))
      (node (ref "U28") (pin "2") (pinfunction "IN_2") (pintype "bidirectional"))
      (node (ref "U3") (pin "10") (pinfunction "AVIN_10") (pintype "bidirectional"))
      (node (ref "U3") (pin "11") (pinfunction "PVIN_11") (pintype "bidirectional"))
      (node (ref "U3") (pin "12") (pinfunction "PVIN_12") (pintype "bidirectional"))
      (node (ref "U3") (pin "13") (pinfunction "EN_13") (pintype "bidirectional"))
      (node (ref "U4") (pin "10") (pinfunction "AVIN_10") (pintype "bidirectional"))
      (node (ref "U4") (pin "11") (pinfunction "PVIN_11") (pintype "bidirectional"))
      (node (ref "U4") (pin "12") (pinfunction "PVIN_12") (pintype "bidirectional"))
      (node (ref "U4") (pin "13") (pinfunction "EN_13") (pintype "bidirectional"))
      (node (ref "U5") (pin "10") (pinfunction "AVIN_10") (pintype "bidirectional"))
      (node (ref "U5") (pin "11") (pinfunction "PVIN_11") (pintype "bidirectional"))
      (node (ref "U5") (pin "12") (pinfunction "PVIN_12") (pintype "bidirectional"))
      (node (ref "U5") (pin "13") (pinfunction "EN_13") (pintype "bidirectional"))
    )
    (net (code "79") (name "VBAT-") (class "Default")
      (node (ref "J1") (pin "18") (pinfunction "VBATT-_18") (pintype "power_in"))
      (node (ref "JP1") (pin "3") (pinfunction "3_3") (pintype "passive"))
      (node (ref "R1") (pin "1") (pinfunction "1_1") (pintype "passive"))
      (node (ref "U18") (pin "2") (pinfunction "CSP_2") (pintype "bidirectional"))
    )
    (net (code "80") (name "VCC_3V3") (class "Default")
      (node (ref "3V3") (pin "TESTPOINT") (pinfunction "TESTPOINT_TESTPOINT") (pintype "bidirectional"))
      (node (ref "C15") (pin "1") (pinfunction "1_1") (pintype "bidirectional"))
      (node (ref "C46") (pin "2") (pinfunction "2_2") (pintype "bidirectional"))
      (node (ref "R17") (pin "2") (pinfunction "2_2") (pintype "passive"))
      (node (ref "R18") (pin "2") (pinfunction "2_2") (pintype "passive"))
      (node (ref "R19") (pin "2") (pinfunction "2_2") (pintype "passive"))
      (node (ref "R2") (pin "2") (pinfunction "2_2") (pintype "passive"))
      (node (ref "U20") (pin "5") (pinfunction "OUT_5") (pintype "bidirectional"))
      (node (ref "U8") (pin "1") (pinfunction "SENSE+_1") (pintype "open_collector"))
    )
    (net (code "81") (name "VCC_5V_1") (class "Default")
      (node (ref "5V_1") (pin "TESTPOINT") (pinfunction "TESTPOINT_TESTPOINT") (pintype "bidirectional"))
      (node (ref "C16") (pin "1") (pinfunction "1_1") (pintype "bidirectional"))
      (node (ref "C47") (pin "2") (pinfunction "2_2") (pintype "bidirectional"))
      (node (ref "R20") (pin "2") (pinfunction "2_2") (pintype "passive"))
      (node (ref "R21") (pin "2") (pinfunction "2_2") (pintype "passive"))
      (node (ref "R22") (pin "2") (pinfunction "2_2") (pintype "passive"))
      (node (ref "R3") (pin "2") (pinfunction "2_2") (pintype "passive"))
      (node (ref "U21") (pin "5") (pinfunction "OUT_5") (pintype "bidirectional"))
      (node (ref "U9") (pin "P1") (pinfunction "SENSE+_P1") (pintype "open_collector"))
    )
    (net (code "82") (name "VCC_5V_2") (class "Default")
      (node (ref "5V_2") (pin "TESTPOINT") (pinfunction "TESTPOINT_TESTPOINT") (pintype "bidirectional"))
      (node (ref "C17") (pin "1") (pinfunction "1_1") (pintype "bidirectional"))
      (node (ref "C48") (pin "2") (pinfunction "2_2") (pintype "bidirectional"))
      (node (ref "R23") (pin "2") (pinfunction "2_2") (pintype "passive"))
      (node (ref "R24") (pin "2") (pinfunction "2_2") (pintype "passive"))
      (node (ref "R25") (pin "2") (pinfunction "2_2") (pintype "passive"))
      (node (ref "R26") (pin "2") (pinfunction "2_2") (pintype "passive"))
      (node (ref "R27") (pin "2") (pinfunction "2_2") (pintype "passive"))
      (node (ref "R28") (pin "2") (pinfunction "2_2") (pintype "passive"))
      (node (ref "R4") (pin "2") (pinfunction "2_2") (pintype "passive"))
      (node (ref "R5") (pin "2") (pinfunction "2_2") (pintype "passive"))
      (node (ref "U10") (pin "P1") (pinfunction "SENSE+_P1") (pintype "open_collector"))
      (node (ref "U11") (pin "P1") (pinfunction "SENSE+_P1") (pintype "open_collector"))
      (node (ref "U22") (pin "5") (pinfunction "OUT_5") (pintype "bidirectional"))
    )
    (net (code "83") (name "VCC_5V_3") (class "Default")
      (node (ref "5V_3") (pin "TESTPOINT") (pinfunction "TESTPOINT_TESTPOINT") (pintype "bidirectional"))
      (node (ref "C18") (pin "1") (pinfunction "1_1") (pintype "bidirectional"))
      (node (ref "C49") (pin "2") (pinfunction "2_2") (pintype "bidirectional"))
      (node (ref "R32") (pin "2") (pinfunction "2_2") (pintype "passive"))
      (node (ref "R33") (pin "2") (pinfunction "2_2") (pintype "passive"))
      (node (ref "R34") (pin "2") (pinfunction "2_2") (pintype "passive"))
      (node (ref "R35") (pin "2") (pinfunction "2_2") (pintype "passive"))
      (node (ref "R36") (pin "2") (pinfunction "2_2") (pintype "passive"))
      (node (ref "R37") (pin "2") (pinfunction "2_2") (pintype "passive"))
      (node (ref "R6") (pin "2") (pinfunction "2_2") (pintype "passive"))
      (node (ref "R7") (pin "2") (pinfunction "2_2") (pintype "passive"))
      (node (ref "U12") (pin "P1") (pinfunction "SENSE+_P1") (pintype "open_collector"))
      (node (ref "U13") (pin "P1") (pinfunction "SENSE+_P1") (pintype "open_collector"))
      (node (ref "U23") (pin "5") (pinfunction "OUT_5") (pintype "bidirectional"))
    )
    (net (code "84") (name "VCC_5V_4") (class "Default")
      (node (ref "5V_4") (pin "TESTPOINT") (pinfunction "TESTPOINT_TESTPOINT") (pintype "bidirectional"))
      (node (ref "C19") (pin "1") (pinfunction "1_1") (pintype "bidirectional"))
      (node (ref "C50") (pin "2") (pinfunction "2_2") (pintype "bidirectional"))
      (node (ref "R29") (pin "2") (pinfunction "2_2") (pintype "passive"))
      (node (ref "R30") (pin "2") (pinfunction "2_2") (pintype "passive"))
      (node (ref "R31") (pin "2") (pinfunction "2_2") (pintype "passive"))
      (node (ref "R38") (pin "2") (pinfunction "2_2") (pintype "passive"))
      (node (ref "R39") (pin "2") (pinfunction "2_2") (pintype "passive"))
      (node (ref "R40") (pin "2") (pinfunction "2_2") (pintype "passive"))
      (node (ref "R8") (pin "2") (pinfunction "2_2") (pintype "passive"))
      (node (ref "R9") (pin "2") (pinfunction "2_2") (pintype "passive"))
      (node (ref "U14") (pin "P1") (pinfunction "SENSE+_P1") (pintype "open_collector"))
      (node (ref "U15") (pin "P1") (pinfunction "SENSE+_P1") (pintype "open_collector"))
      (node (ref "U24") (pin "5") (pinfunction "OUT_5") (pintype "bidirectional"))
    )
    (net (code "85") (name "VCC_BACKPLANE") (class "Default")
      (node (ref "C1") (pin "1") (pinfunction "1_1") (pintype "bidirectional"))
      (node (ref "C23") (pin "1") (pinfunction "1_1") (pintype "bidirectional"))
      (node (ref "J1") (pin "13") (pinfunction "VCC_BACKPLANE_13") (pintype "power_in"))
      (node (ref "J1") (pin "2") (pinfunction "VCC_CONTROLLER_2") (pintype "power_in"))
      (node (ref "J3") (pin "6") (pinfunction "VCC_6") (pintype "bidirectional"))
      (node (ref "R15") (pin "2") (pinfunction "2_2") (pintype "passive"))
      (node (ref "R16") (pin "2") (pinfunction "2_2") (pintype "passive"))
      (node (ref "R2") (pin "1") (pinfunction "1_1") (pintype "passive"))
      (node (ref "R41") (pin "2") (pinfunction "2_2") (pintype "passive"))
      (node (ref "R42") (pin "2") (pinfunction "2_2") (pintype "passive"))
      (node (ref "R43") (pin "2") (pinfunction "2_2") (pintype "passive"))
      (node (ref "SJ1") (pin "1") (pinfunction "1_1") (pintype "passive"))
      (node (ref "U25") (pin "2") (pinfunction "A1_2") (pintype "bidirectional"))
      (node (ref "U25") (pin "20") (pinfunction "VCC_20") (pintype "bidirectional"))
      (node (ref "U29") (pin "8") (pinfunction "VCC_8") (pintype "bidirectional"))
      (node (ref "U6") (pin "20") (pinfunction "VCC_20") (pintype "bidirectional"))
      (node (ref "U7") (pin "1") (pinfunction "A0_1") (pintype "bidirectional"))
      (node (ref "U7") (pin "20") (pinfunction "VCC_20") (pintype "bidirectional"))
      (node (ref "U8") (pin "6") (pinfunction "SENSE-_6") (pintype "open_collector"))
    )
    (net (code "86") (name "VCC_LINUX") (class "Default")
      (node (ref "C2") (pin "1") (pinfunction "1_1") (pintype "bidirectional"))
      (node (ref "J1") (pin "4") (pinfunction "VCC_LINUX_4") (pintype "power_in"))
      (node (ref "R3") (pin "1") (pinfunction "1_1") (pintype "passive"))
      (node (ref "U9") (pin "P8") (pinfunction "SENSE-_P8") (pintype "open_collector"))
    )
    (net (code "87") (name "VCC_MOD0") (class "Default")
      (node (ref "C3") (pin "1") (pinfunction "1_1") (pintype "bidirectional"))
      (node (ref "J1") (pin "7") (pinfunction "VCC_MOD0_7") (pintype "power_in"))
      (node (ref "R4") (pin "1") (pinfunction "1_1") (pintype "passive"))
      (node (ref "U10") (pin "P8") (pinfunction "SENSE-_P8") (pintype "open_collector"))
    )
    (net (code "88") (name "VCC_MOD1") (class "Default")
      (node (ref "C4") (pin "1") (pinfunction "1_1") (pintype "bidirectional"))
      (node (ref "J1") (pin "8") (pinfunction "VCC_MOD1_8") (pintype "power_in"))
      (node (ref "R5") (pin "1") (pinfunction "1_1") (pintype "passive"))
      (node (ref "U11") (pin "P8") (pinfunction "SENSE-_P8") (pintype "open_collector"))
    )
    (net (code "89") (name "VCC_MOD2") (class "Default")
      (node (ref "C5") (pin "1") (pinfunction "1_1") (pintype "bidirectional"))
      (node (ref "J1") (pin "9") (pinfunction "VCC_MOD2_9") (pintype "power_in"))
      (node (ref "R6") (pin "1") (pinfunction "1_1") (pintype "passive"))
      (node (ref "U12") (pin "P8") (pinfunction "SENSE-_P8") (pintype "open_collector"))
    )
    (net (code "90") (name "VCC_MOD5") (class "Default")
      (node (ref "C6") (pin "1") (pinfunction "1_1") (pintype "bidirectional"))
      (node (ref "J1") (pin "10") (pinfunction "VCC_MOD5_10") (pintype "power_in"))
      (node (ref "R7") (pin "1") (pinfunction "1_1") (pintype "passive"))
      (node (ref "U13") (pin "P8") (pinfunction "SENSE-_P8") (pintype "open_collector"))
    )
    (net (code "91") (name "VCC_MOD6") (class "Default")
      (node (ref "C7") (pin "1") (pinfunction "1_1") (pintype "bidirectional"))
      (node (ref "J1") (pin "11") (pinfunction "VCC_MOD6_11") (pintype "power_in"))
      (node (ref "R8") (pin "1") (pinfunction "1_1") (pintype "passive"))
      (node (ref "U14") (pin "P8") (pinfunction "SENSE-_P8") (pintype "open_collector"))
    )
    (net (code "92") (name "VCC_MOD7") (class "Default")
      (node (ref "C8") (pin "1") (pinfunction "1_1") (pintype "bidirectional"))
      (node (ref "J1") (pin "12") (pinfunction "VCC_MOD7_12") (pintype "power_in"))
      (node (ref "R9") (pin "1") (pinfunction "1_1") (pintype "passive"))
      (node (ref "U15") (pin "P8") (pinfunction "SENSE-_P8") (pintype "open_collector"))
    )
    (net (code "93") (name "VSOL+") (class "Default")
      (node (ref "C20") (pin "1") (pinfunction "1_1") (pintype "bidirectional"))
      (node (ref "J1") (pin "19") (pinfunction "VSOL+_19") (pintype "power_in"))
      (node (ref "JP1") (pin "2") (pinfunction "2_2") (pintype "passive"))
      (node (ref "R11") (pin "2") (pinfunction "2_2") (pintype "passive"))
      (node (ref "U26") (pin "P1") (pinfunction "SENSE+_P1") (pintype "open_collector"))
    )
    (net (code "94") (name "VSOL_SENSE") (class "Default")
      (node (ref "C40") (pin "P$1") (pinfunction "1_P$1") (pintype "bidirectional"))
      (node (ref "R11") (pin "1") (pinfunction "1_1") (pintype "passive"))
      (node (ref "R57") (pin "2") (pinfunction "2_2") (pintype "passive"))
      (node (ref "U16") (pin "1") (pinfunction "VIN_1") (pintype "bidirectional"))
      (node (ref "U16") (pin "3") (pinfunction "~{SHDN}_3") (pintype "bidirectional"))
      (node (ref "U17") (pin "4") (pinfunction "V+_4") (pintype "bidirectional"))
      (node (ref "U26") (pin "P8") (pinfunction "SENSE-_P8") (pintype "open_collector"))
    )
    (net (code "95") (name "WDI") (class "Default")
      (node (ref "J1") (pin "16") (pinfunction "WDI_16") (pintype "power_in"))
      (node (ref "U27") (pin "6") (pinfunction "WDI_6") (pintype "bidirectional"))
    )
    (net (code "96") (name "unconnected-(U16-NTC-Pad8)") (class "Default")
      (node (ref "U16") (pin "8") (pinfunction "NTC_8") (pintype "bidirectional"))
    )
    (net (code "97") (name "unconnected-(U18-AIN1-Pad9)") (class "Default")
      (node (ref "U18") (pin "9") (pinfunction "AIN1_9") (pintype "bidirectional"))
    )
    (net (code "98") (name "unconnected-(U18-AIN2-Pad10)") (class "Default")
      (node (ref "U18") (pin "10") (pinfunction "AIN2_10") (pintype "bidirectional"))
    )
    (net (code "99") (name "unconnected-(U18-THRM-Pad14)") (class "Default")
      (node (ref "U18") (pin "14") (pinfunction "THRM_14") (pintype "bidirectional"))
    )
    (net (code "100") (name "unconnected-(U20-FLG-Pad4)") (class "Default")
      (node (ref "U20") (pin "4") (pinfunction "FLG_4") (pintype "bidirectional"))
    )
    (net (code "101") (name "unconnected-(U21-FLG-Pad4)") (class "Default")
      (node (ref "U21") (pin "4") (pinfunction "FLG_4") (pintype "bidirectional"))
    )
    (net (code "102") (name "unconnected-(U22-FLG-Pad4)") (class "Default")
      (node (ref "U22") (pin "4") (pinfunction "FLG_4") (pintype "bidirectional"))
    )
    (net (code "103") (name "unconnected-(U23-FLG-Pad4)") (class "Default")
      (node (ref "U23") (pin "4") (pinfunction "FLG_4") (pintype "bidirectional"))
    )
    (net (code "104") (name "unconnected-(U24-FLG-Pad4)") (class "Default")
      (node (ref "U24") (pin "4") (pinfunction "FLG_4") (pintype "bidirectional"))
    )
    (net (code "105") (name "unconnected-(U25-SC1-Pad9)") (class "Default")
      (node (ref "U25") (pin "9") (pinfunction "SC1_9") (pintype "bidirectional"))
    )
    (net (code "106") (name "unconnected-(U25-SC2-Pad13)") (class "Default")
      (node (ref "U25") (pin "13") (pinfunction "SC2_13") (pintype "bidirectional"))
    )
    (net (code "107") (name "unconnected-(U25-SC3-Pad16)") (class "Default")
      (node (ref "U25") (pin "16") (pinfunction "SC3_16") (pintype "bidirectional"))
    )
    (net (code "108") (name "unconnected-(U25-SD1-Pad8)") (class "Default")
      (node (ref "U25") (pin "8") (pinfunction "SD1_8") (pintype "bidirectional"))
    )
    (net (code "109") (name "unconnected-(U25-SD2-Pad12)") (class "Default")
      (node (ref "U25") (pin "12") (pinfunction "SD2_12") (pintype "bidirectional"))
    )
    (net (code "110") (name "unconnected-(U25-SD3-Pad15)") (class "Default")
      (node (ref "U25") (pin "15") (pinfunction "SD3_15") (pintype "bidirectional"))
    )
    (net (code "111") (name "unconnected-(U25-~{INT1}-Pad7)") (class "Default")
      (node (ref "U25") (pin "7") (pinfunction "~{INT1}_7") (pintype "bidirectional"))
    )
    (net (code "112") (name "unconnected-(U25-~{INT2}-Pad11)") (class "Default")
      (node (ref "U25") (pin "11") (pinfunction "~{INT2}_11") (pintype "bidirectional"))
    )
    (net (code "113") (name "unconnected-(U25-~{INT3}-Pad14)") (class "Default")
      (node (ref "U25") (pin "14") (pinfunction "~{INT3}_14") (pintype "bidirectional"))
    )
    (net (code "114") (name "~{INT}") (class "Default")
      (node (ref "J1") (pin "6") (pinfunction "~{SMBALERT}_6") (pintype "bidirectional"))
      (node (ref "R13") (pin "2") (pinfunction "2_2") (pintype "passive"))
      (node (ref "U25") (pin "17") (pinfunction "~{INT}_17") (pintype "bidirectional"))
      (node (ref "U6") (pin "17") (pinfunction "~{INT}_17") (pintype "bidirectional"))
      (node (ref "U7") (pin "17") (pinfunction "~{INT}_17") (pintype "bidirectional"))
    )
  )
)
